# pcb-pick-plaz-control_v1e.net
KiCad netlist of a schematic drawn in EAGLE
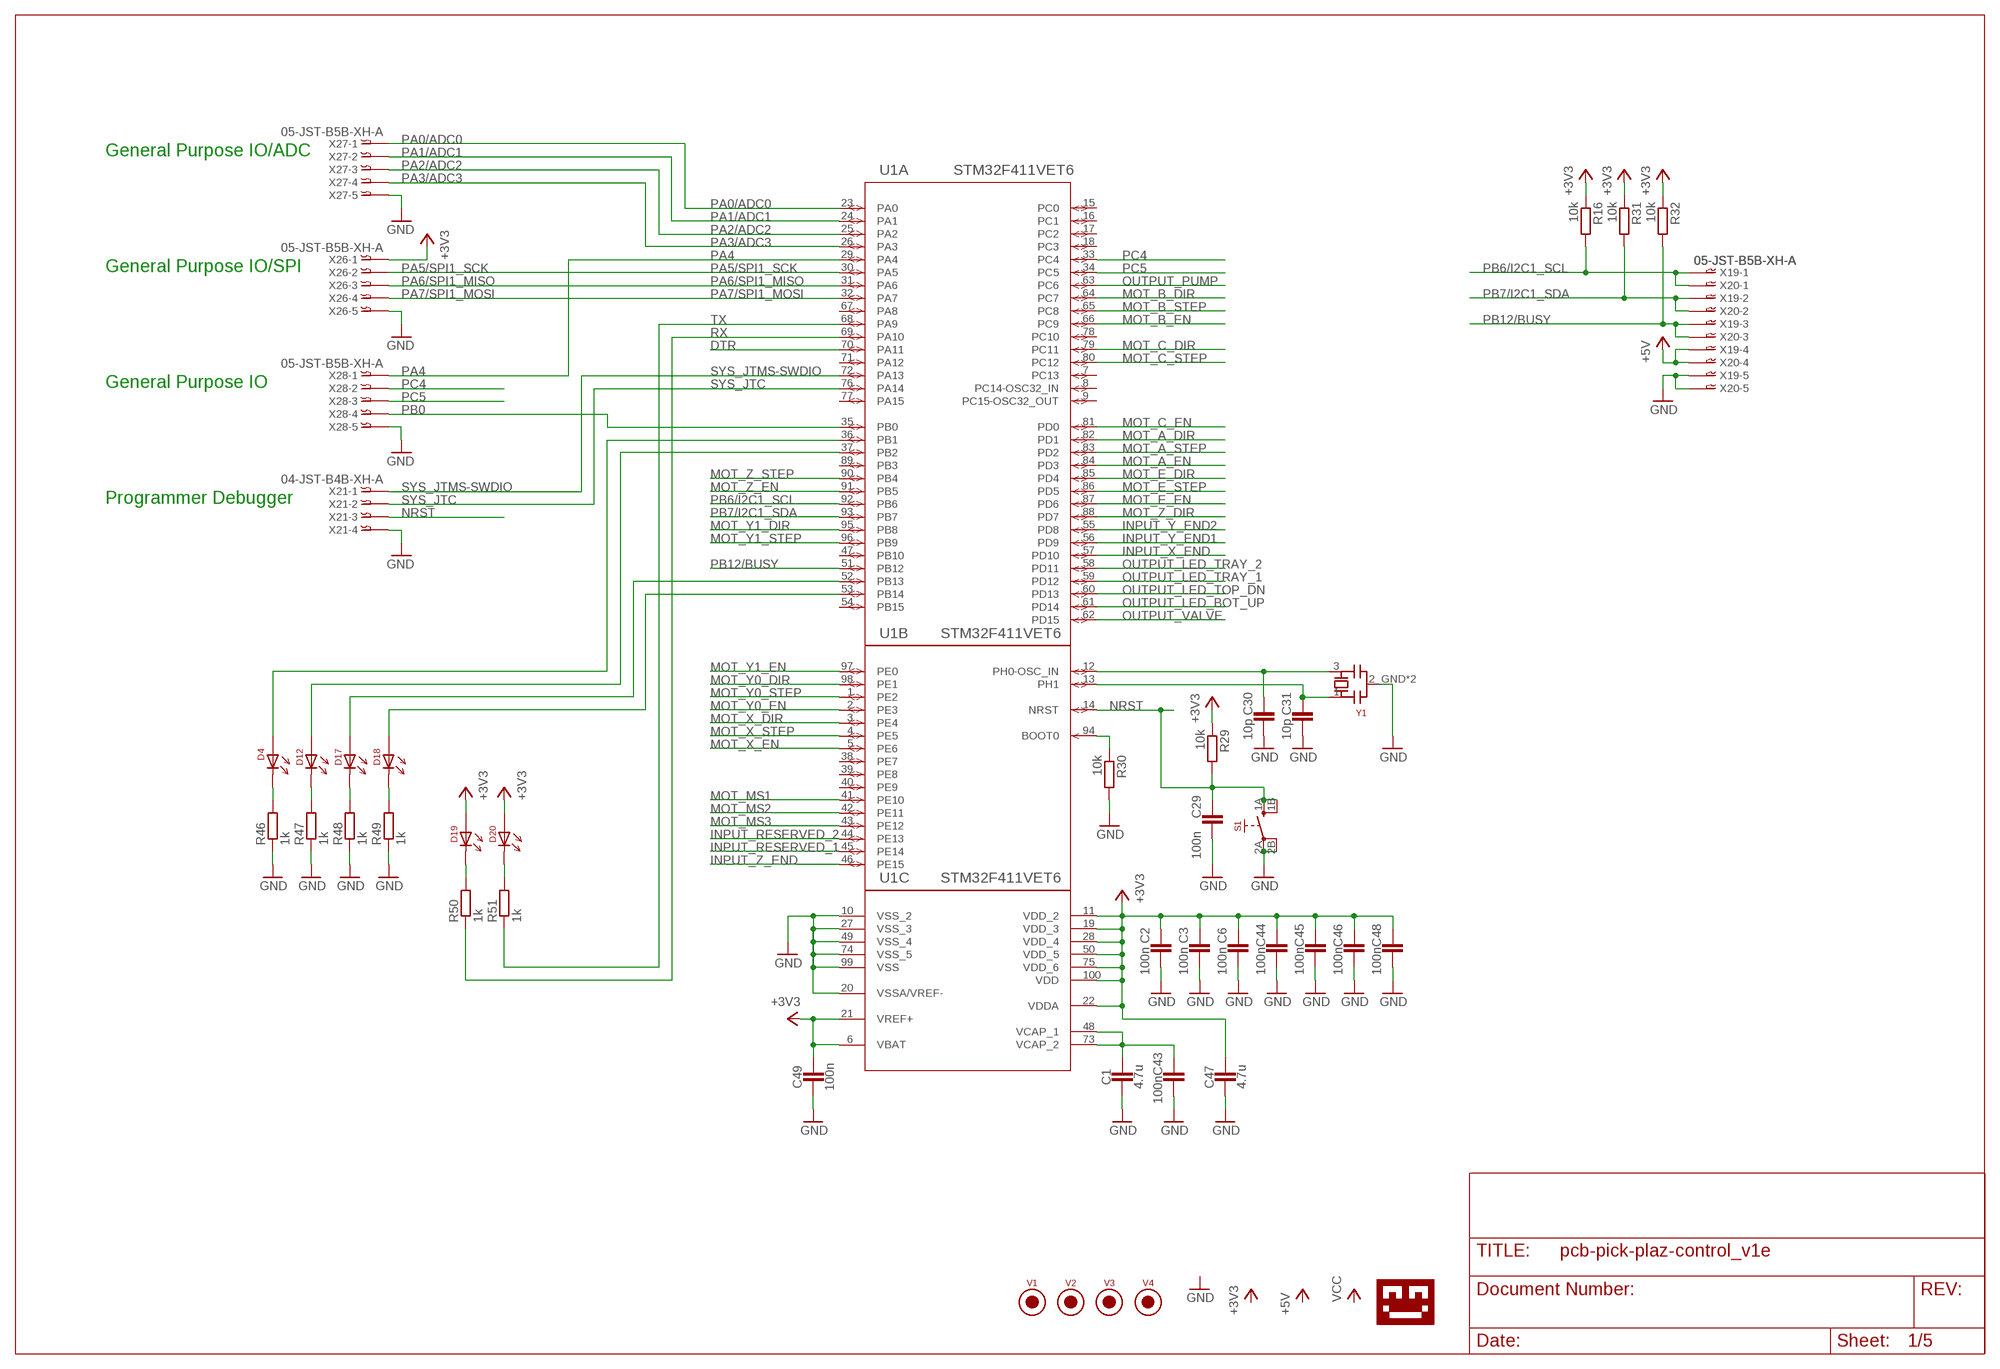
[diagram p0: schematic, sheet 1]
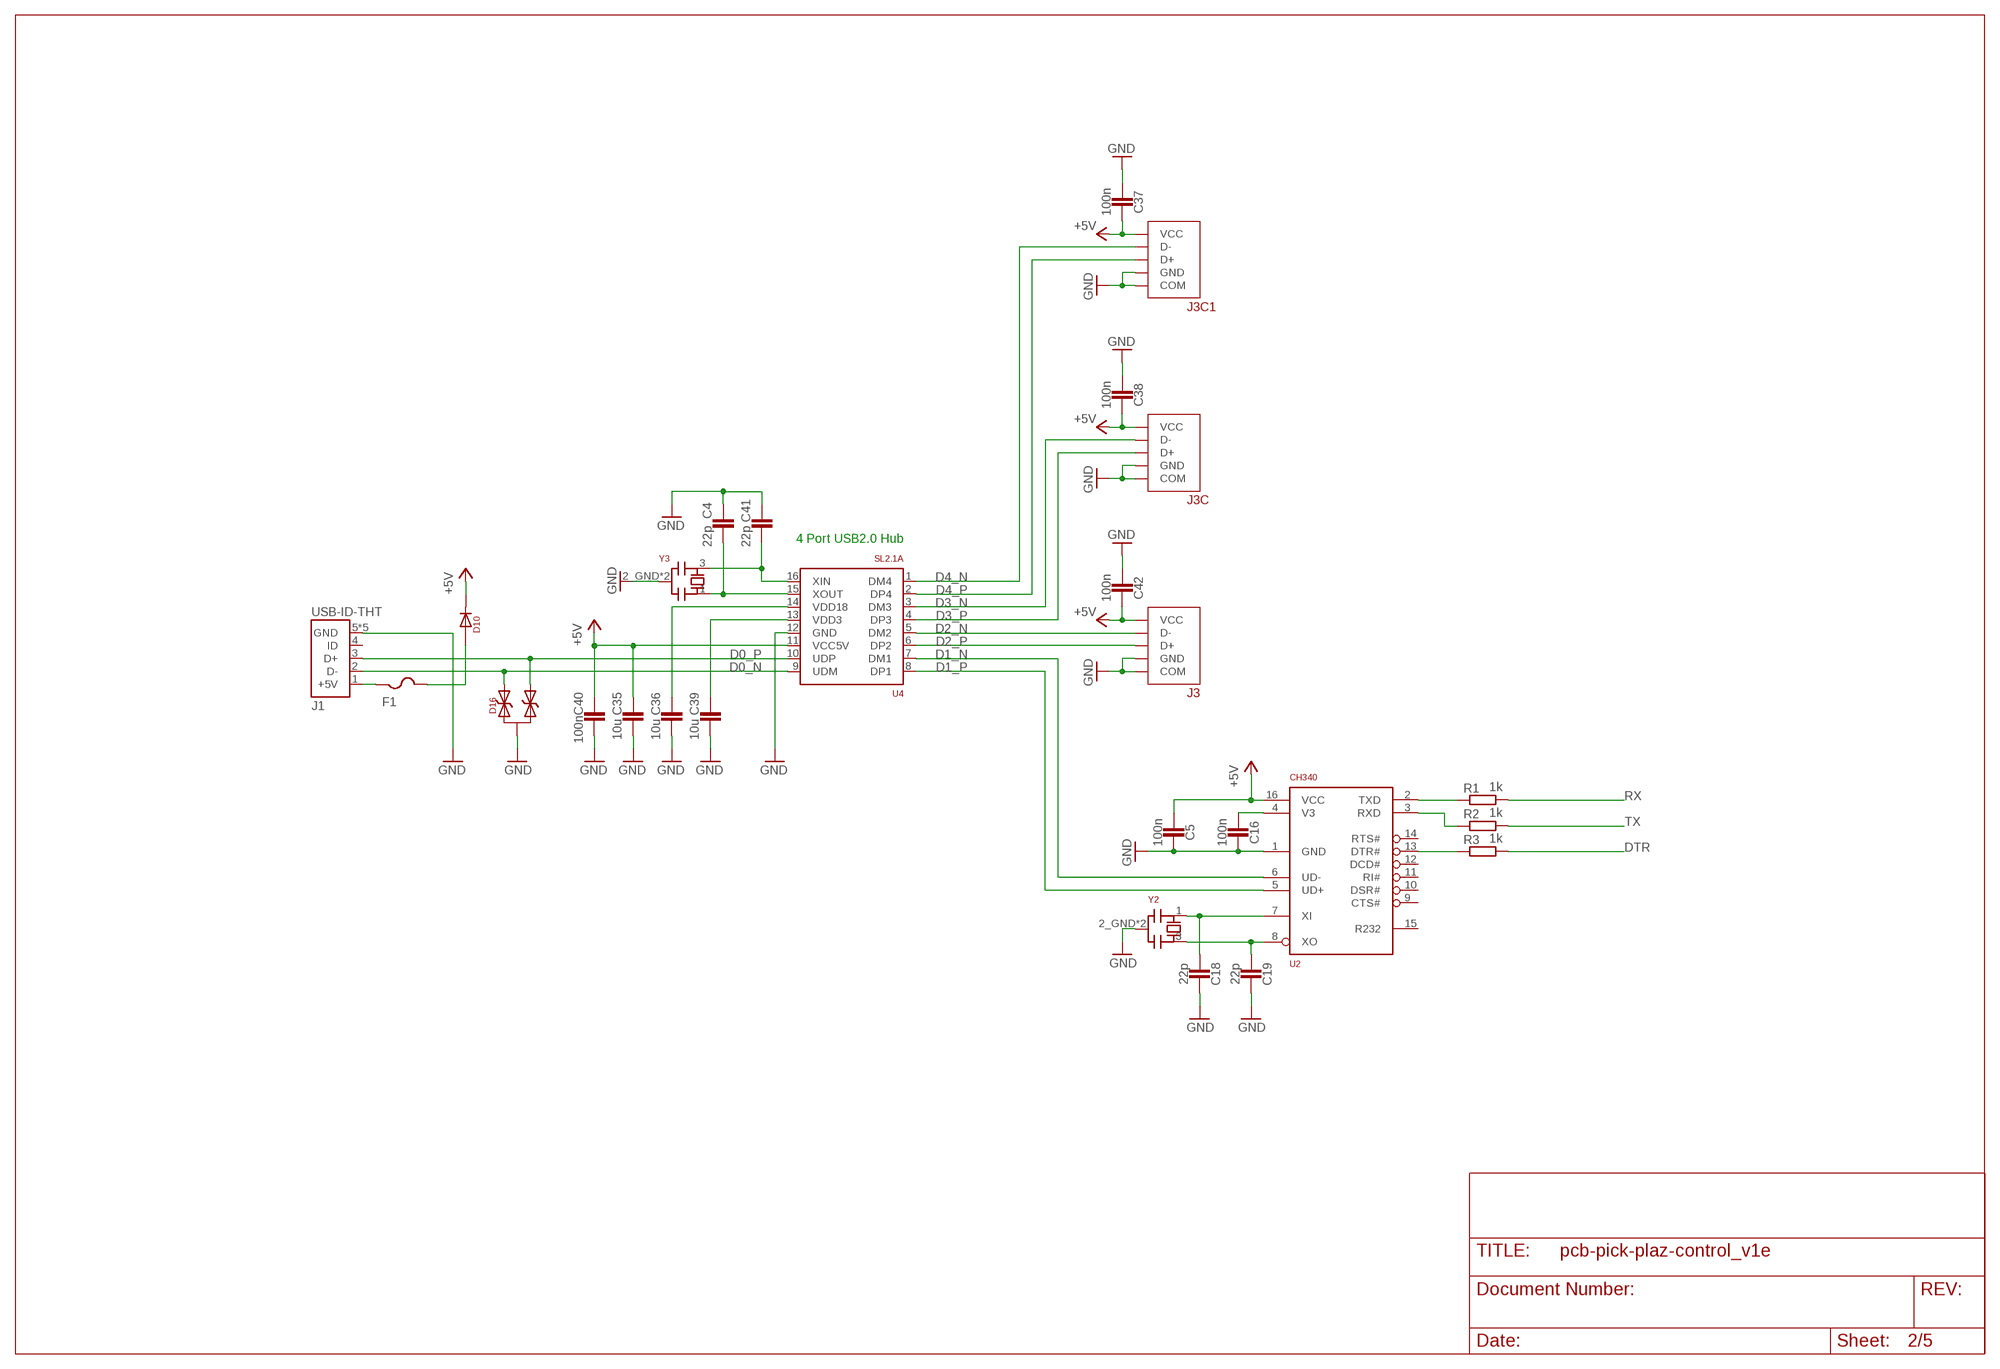
[diagram p1: schematic, sheet 2]
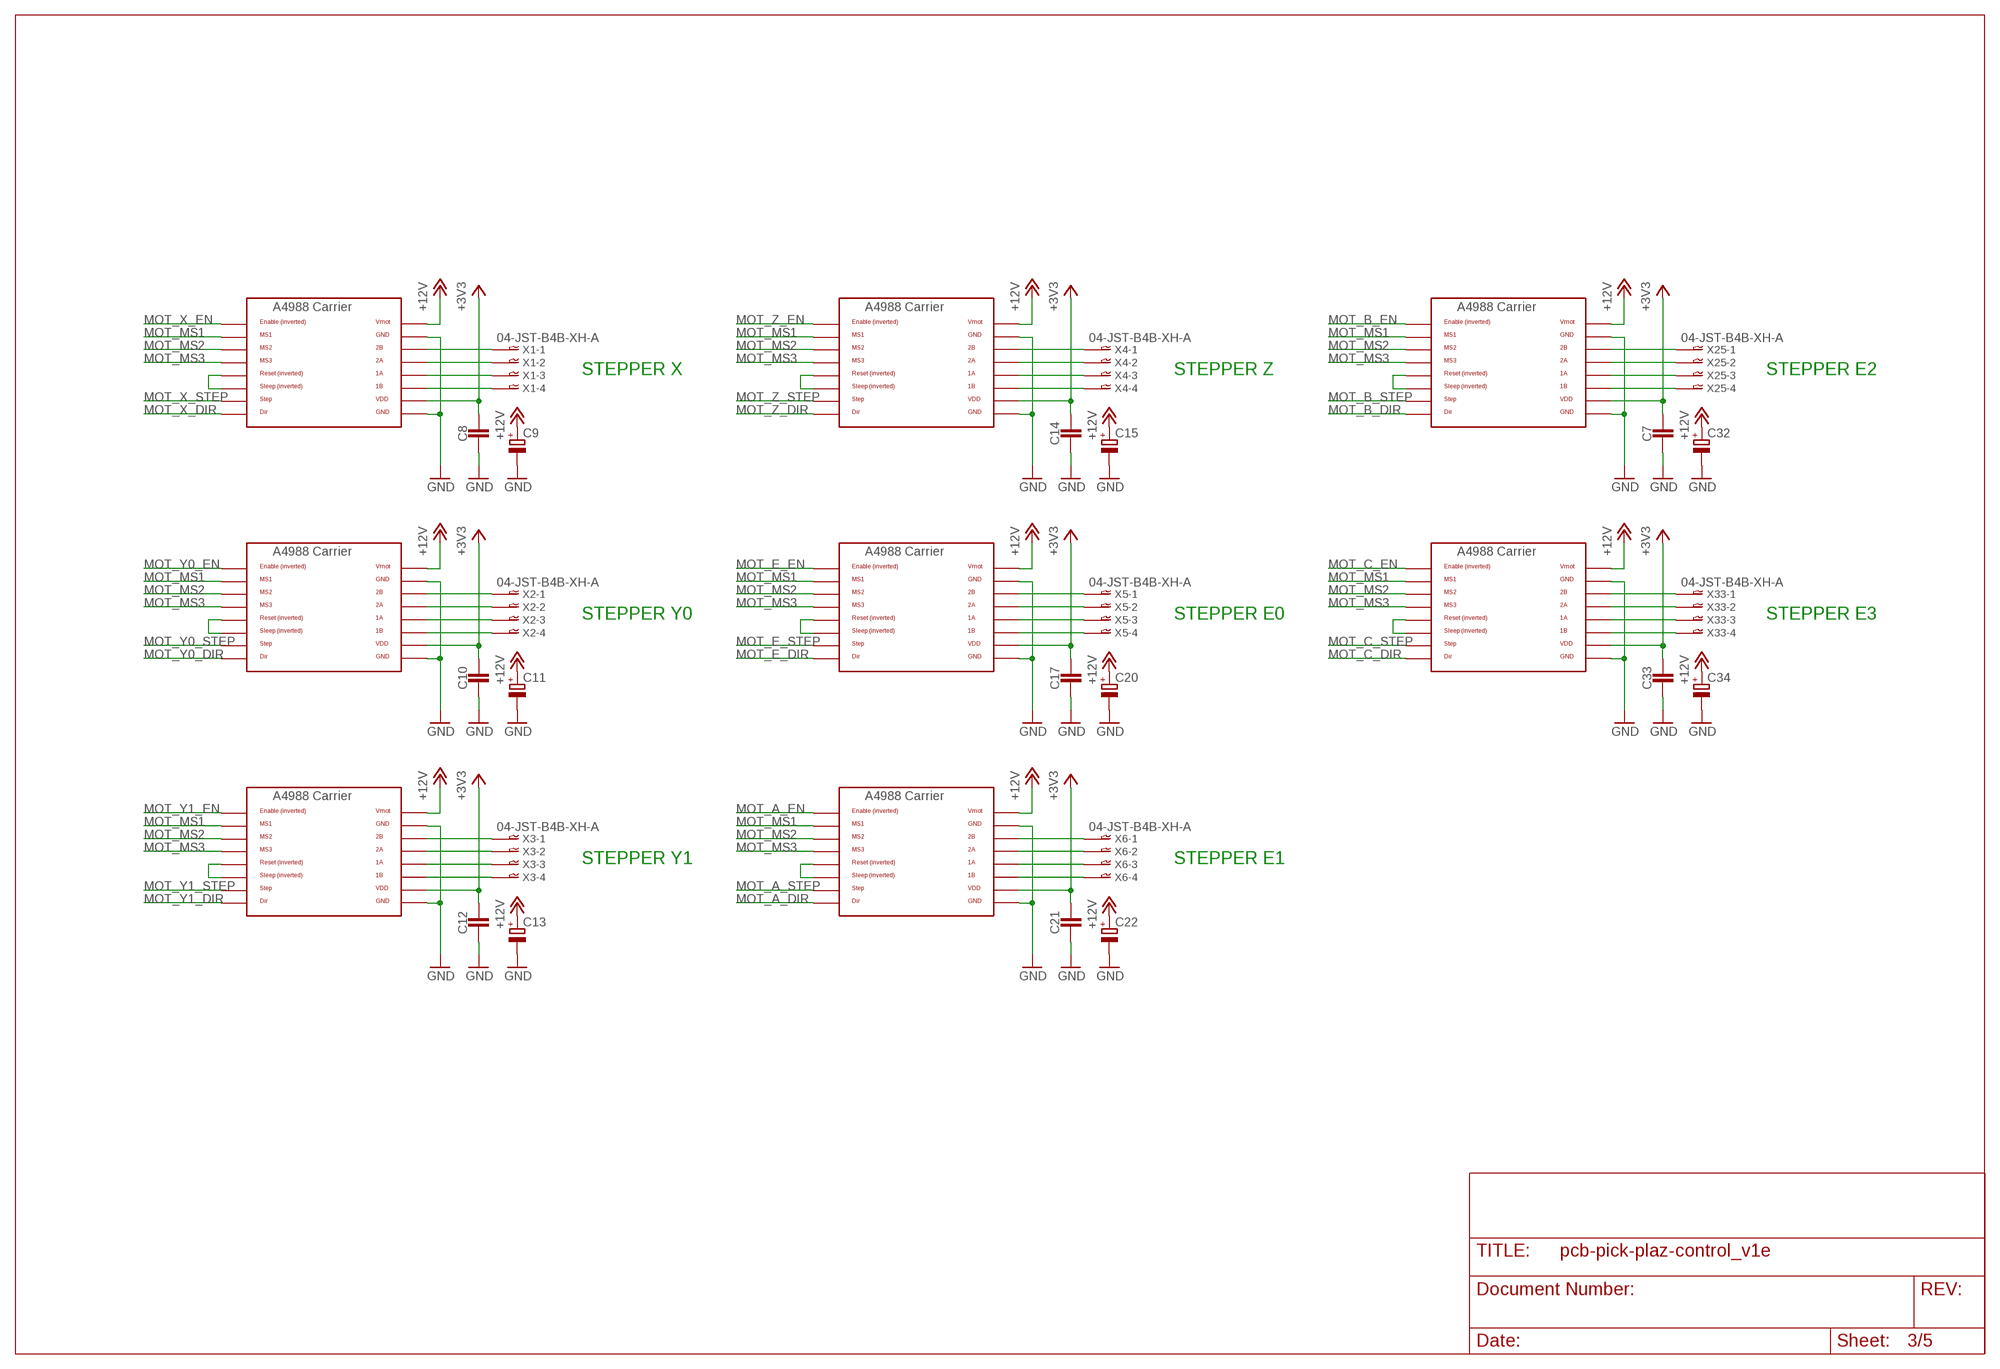
[diagram p2: schematic, sheet 3]
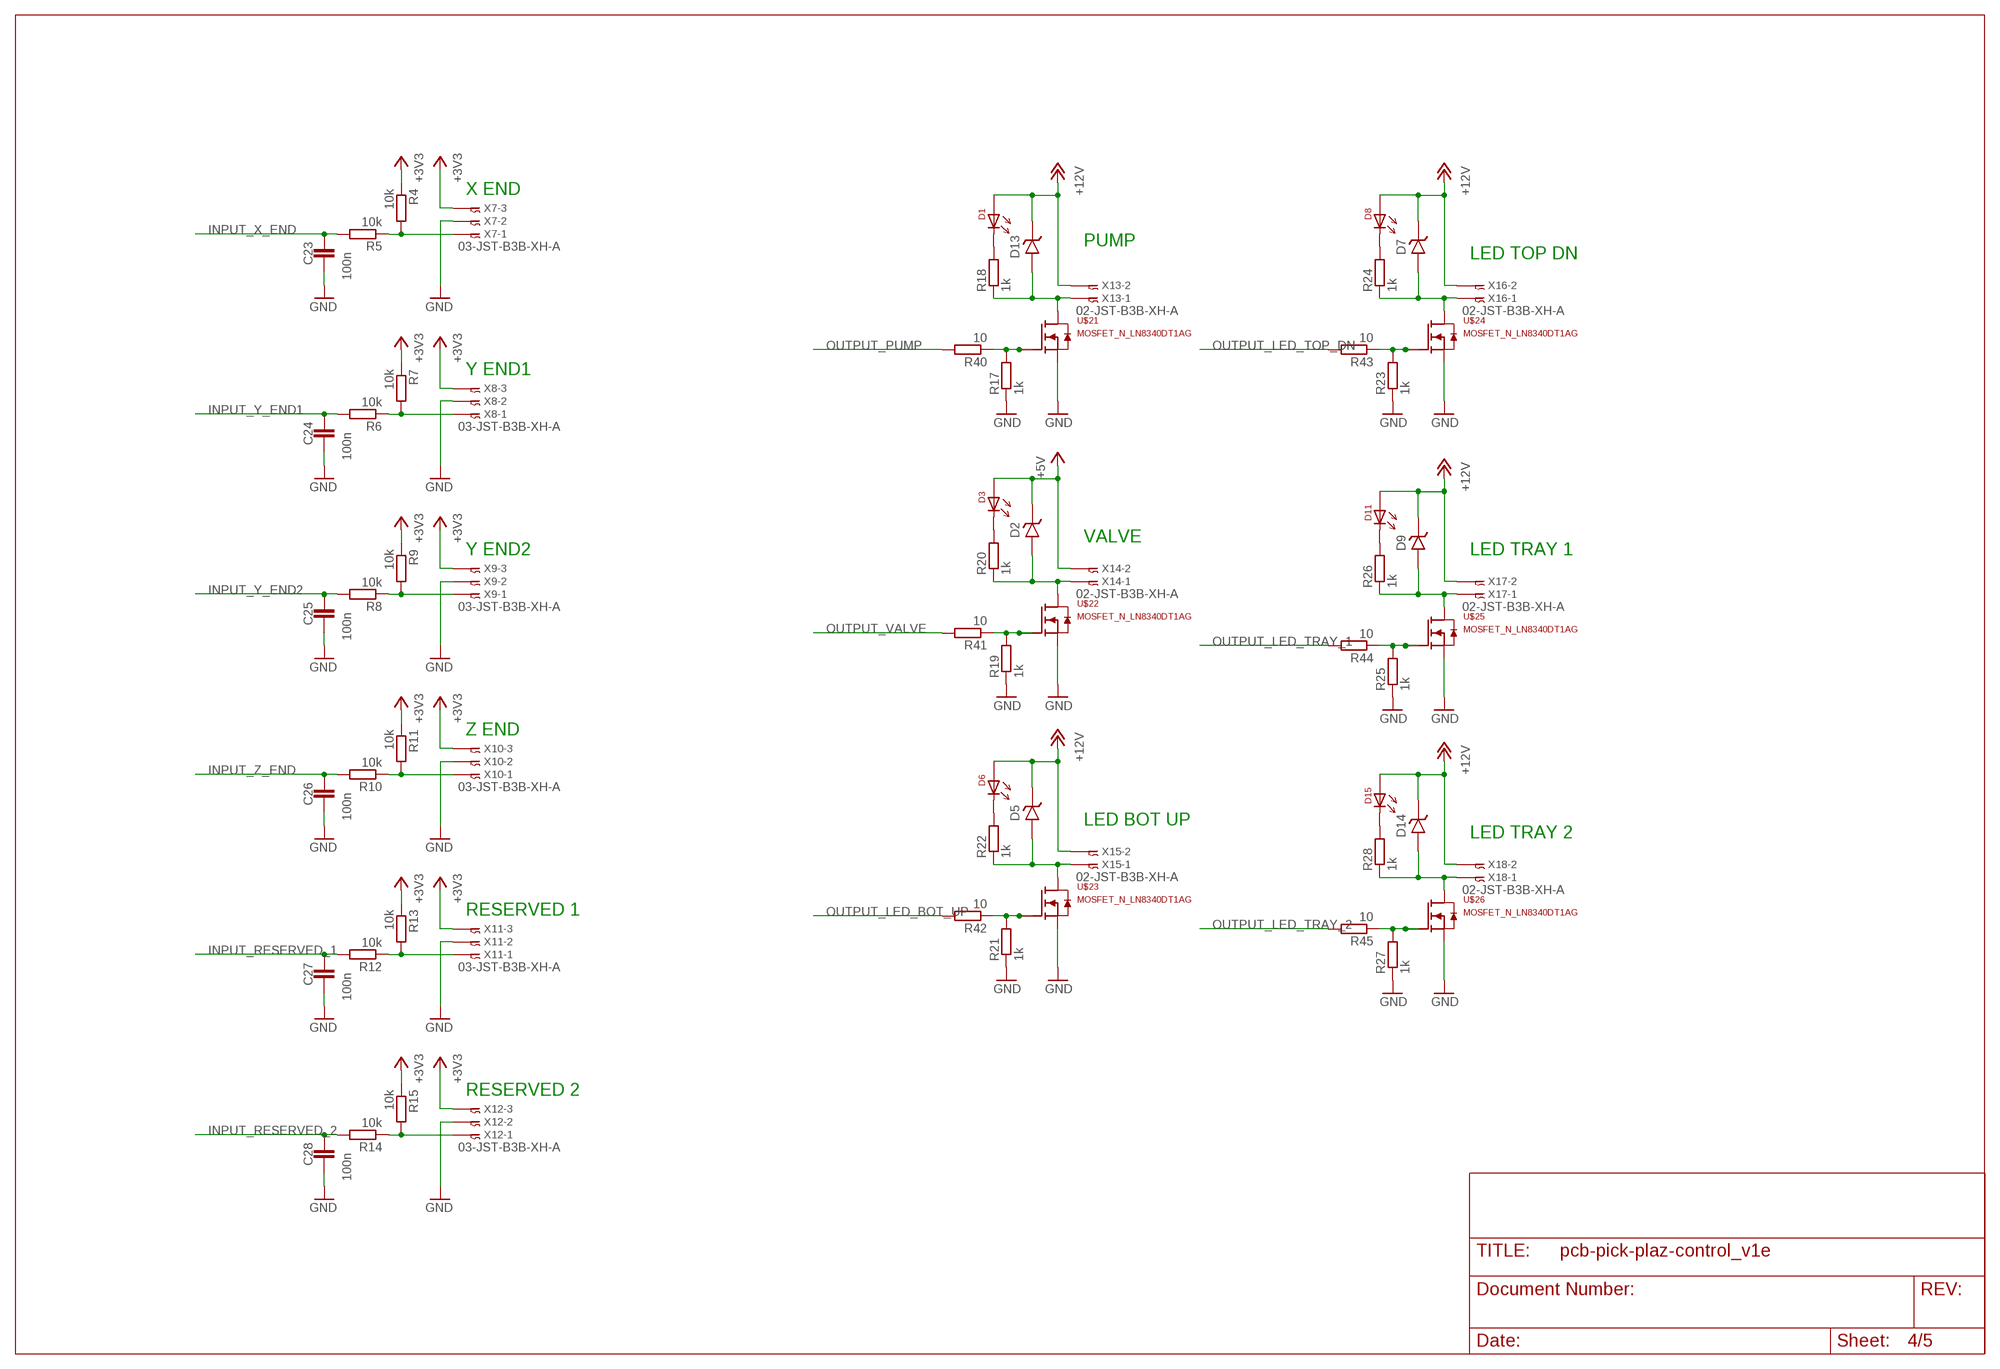
[diagram p3: schematic, sheet 4]
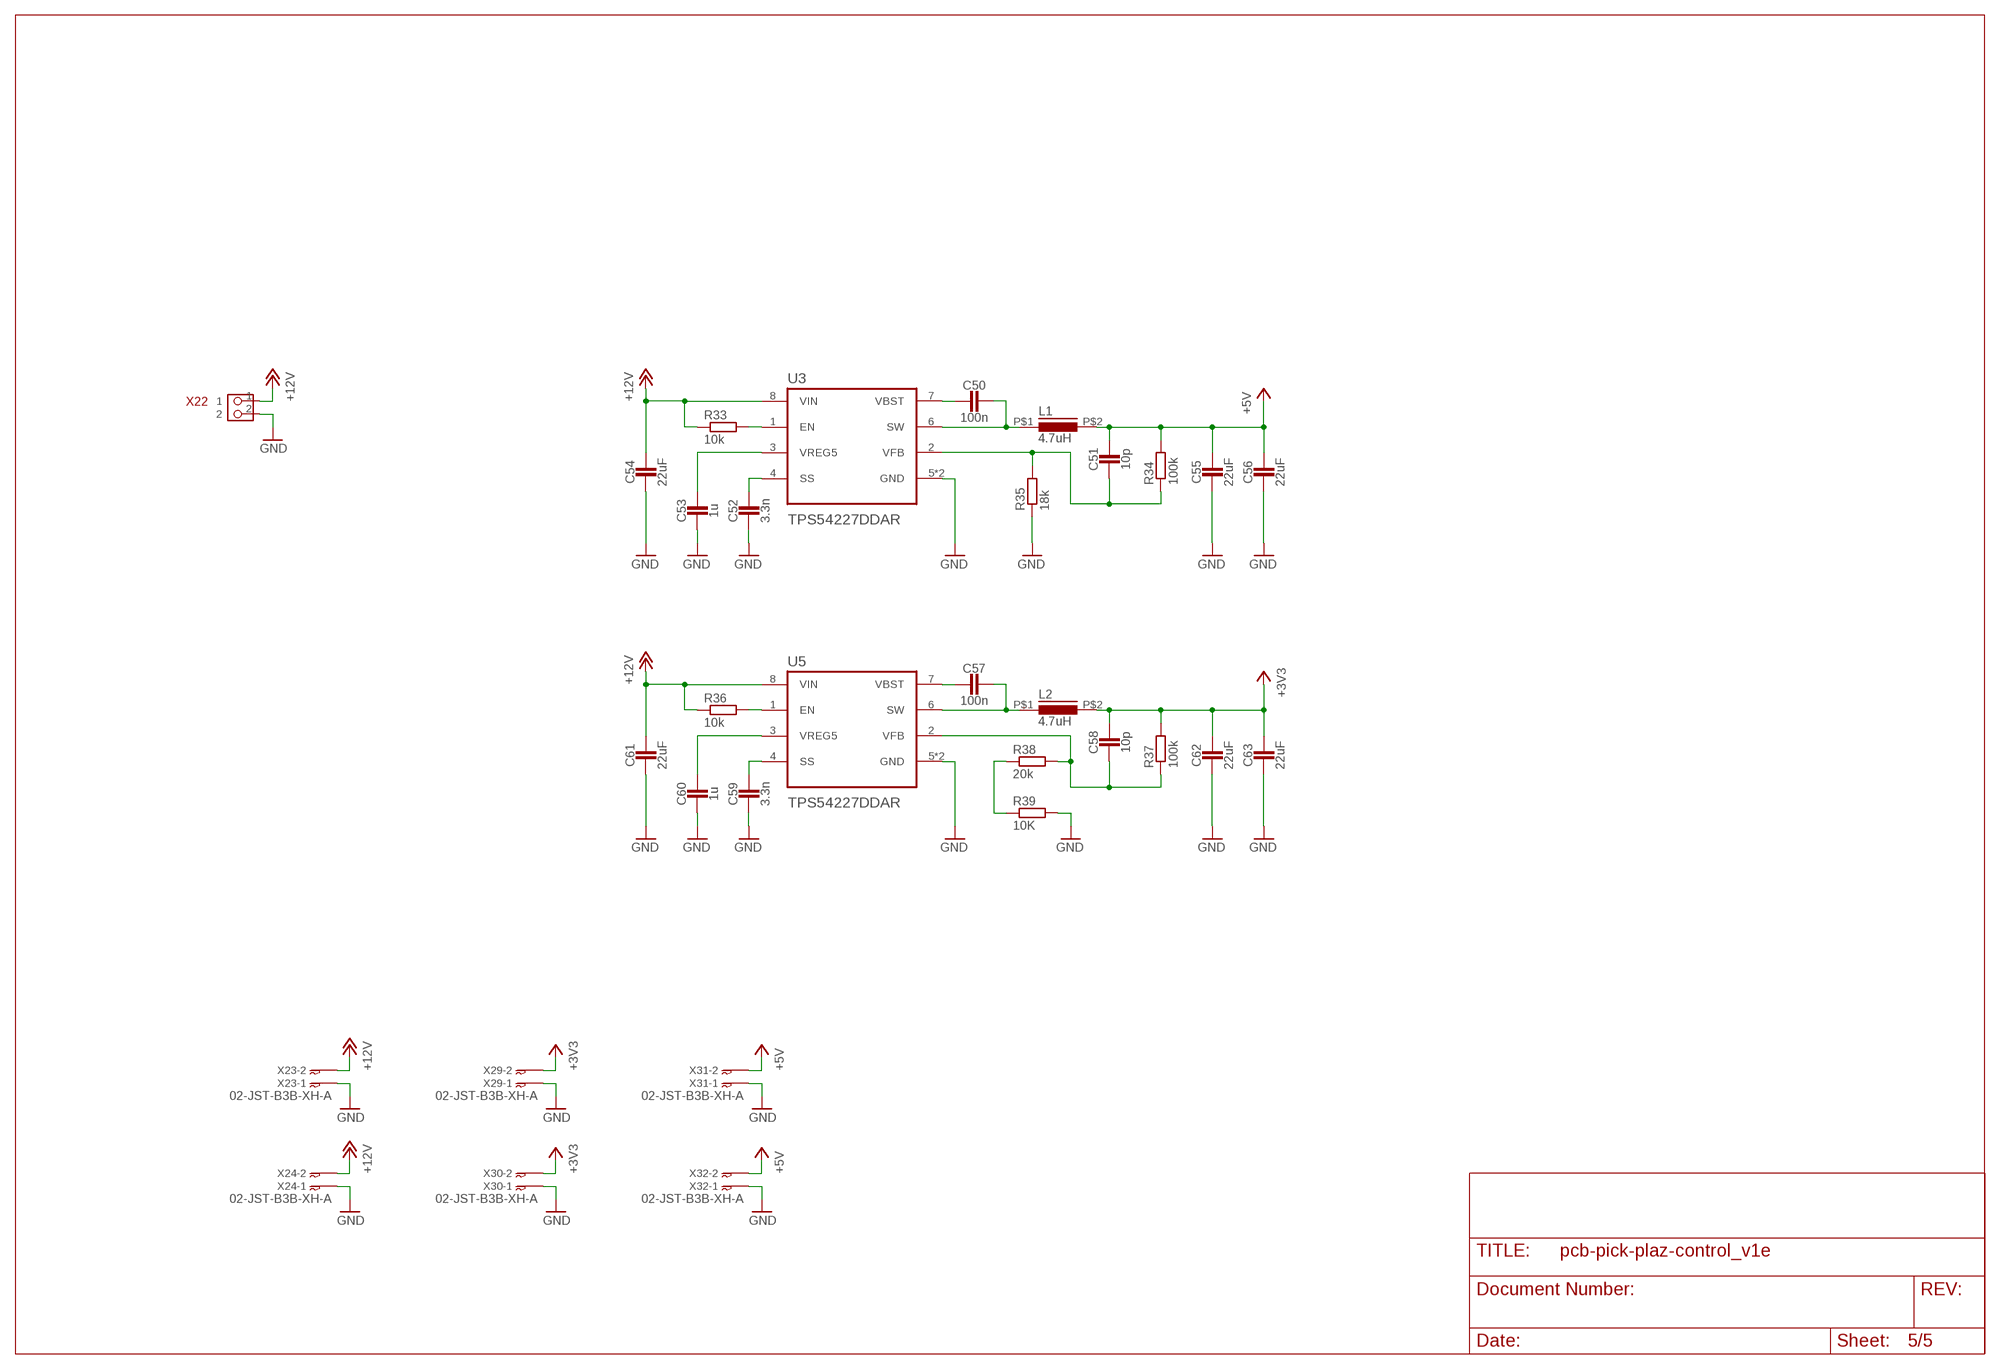
[diagram p4: schematic, sheet 5]

(export (version "E")
  (design (tool "Eeschema 10.0.6"))
  (components
    (comp (ref "C23")
      (value "100n")
      (footprint "eagle-import:0603_CAP")
      (libsource (lib "eagle-import") (part "CAPACITOR0603_CAP"))
    )
    (comp (ref "C24")
      (value "100n")
      (footprint "eagle-import:0603_CAP")
      (libsource (lib "eagle-import") (part "CAPACITOR0603_CAP"))
    )
    (comp (ref "C25")
      (value "100n")
      (footprint "eagle-import:0603_CAP")
      (libsource (lib "eagle-import") (part "CAPACITOR0603_CAP"))
    )
    (comp (ref "C26")
      (value "100n")
      (footprint "eagle-import:0603_CAP")
      (libsource (lib "eagle-import") (part "CAPACITOR0603_CAP"))
    )
    (comp (ref "C27")
      (value "100n")
      (footprint "eagle-import:0603_CAP")
      (libsource (lib "eagle-import") (part "CAPACITOR0603_CAP"))
    )
    (comp (ref "C28")
      (value "100n")
      (footprint "eagle-import:0603_CAP")
      (libsource (lib "eagle-import") (part "CAPACITOR0603_CAP"))
    )
    (comp (ref "D1")
      (value "LED-0805")
      (footprint "eagle-import:0805-DOT")
      (libsource (lib "eagle-import") (part "LED-0805"))
    )
    (comp (ref "D2")
      (value "DIODE_ZENERSOD123")
      (footprint "eagle-import:SOD123")
      (libsource (lib "eagle-import") (part "DIODE_ZENERSOD123"))
    )
    (comp (ref "D3")
      (value "LED-0805")
      (footprint "eagle-import:0805-DOT")
      (libsource (lib "eagle-import") (part "LED-0805"))
    )
    (comp (ref "D5")
      (value "DIODE_ZENERSOD123")
      (footprint "eagle-import:SOD123")
      (libsource (lib "eagle-import") (part "DIODE_ZENERSOD123"))
    )
    (comp (ref "D6")
      (value "LED-0805")
      (footprint "eagle-import:0805-DOT")
      (libsource (lib "eagle-import") (part "LED-0805"))
    )
    (comp (ref "D7")
      (value "DIODE_ZENERSOD123")
      (footprint "eagle-import:SOD123")
      (libsource (lib "eagle-import") (part "DIODE_ZENERSOD123"))
    )
    (comp (ref "D8")
      (value "LED-0805")
      (footprint "eagle-import:0805-DOT")
      (libsource (lib "eagle-import") (part "LED-0805"))
    )
    (comp (ref "D9")
      (value "DIODE_ZENERSOD123")
      (footprint "eagle-import:SOD123")
      (libsource (lib "eagle-import") (part "DIODE_ZENERSOD123"))
    )
    (comp (ref "D11")
      (value "LED-0805")
      (footprint "eagle-import:0805-DOT")
      (libsource (lib "eagle-import") (part "LED-0805"))
    )
    (comp (ref "D13")
      (value "DIODE_ZENERSOD123")
      (footprint "eagle-import:SOD123")
      (libsource (lib "eagle-import") (part "DIODE_ZENERSOD123"))
    )
    (comp (ref "D14")
      (value "DIODE_ZENERSOD123")
      (footprint "eagle-import:SOD123")
      (libsource (lib "eagle-import") (part "DIODE_ZENERSOD123"))
    )
    (comp (ref "D15")
      (value "LED-0805")
      (footprint "eagle-import:0805-DOT")
      (libsource (lib "eagle-import") (part "LED-0805"))
    )
    (comp (ref "R4")
      (value "10k")
      (footprint "eagle-import:0603-RES")
      (libsource (lib "eagle-import") (part "RESISTOR0603_RES"))
    )
    (comp (ref "R5")
      (value "10k")
      (footprint "eagle-import:0603-RES")
      (libsource (lib "eagle-import") (part "RESISTOR0603_RES"))
    )
    (comp (ref "R6")
      (value "10k")
      (footprint "eagle-import:0603-RES")
      (libsource (lib "eagle-import") (part "RESISTOR0603_RES"))
    )
    (comp (ref "R7")
      (value "10k")
      (footprint "eagle-import:0603-RES")
      (libsource (lib "eagle-import") (part "RESISTOR0603_RES"))
    )
    (comp (ref "R8")
      (value "10k")
      (footprint "eagle-import:0603-RES")
      (libsource (lib "eagle-import") (part "RESISTOR0603_RES"))
    )
    (comp (ref "R9")
      (value "10k")
      (footprint "eagle-import:0603-RES")
      (libsource (lib "eagle-import") (part "RESISTOR0603_RES"))
    )
    (comp (ref "R10")
      (value "10k")
      (footprint "eagle-import:0603-RES")
      (libsource (lib "eagle-import") (part "RESISTOR0603_RES"))
    )
    (comp (ref "R11")
      (value "10k")
      (footprint "eagle-import:0603-RES")
      (libsource (lib "eagle-import") (part "RESISTOR0603_RES"))
    )
    (comp (ref "R12")
      (value "10k")
      (footprint "eagle-import:0603-RES")
      (libsource (lib "eagle-import") (part "RESISTOR0603_RES"))
    )
    (comp (ref "R13")
      (value "10k")
      (footprint "eagle-import:0603-RES")
      (libsource (lib "eagle-import") (part "RESISTOR0603_RES"))
    )
    (comp (ref "R14")
      (value "10k")
      (footprint "eagle-import:0603-RES")
      (libsource (lib "eagle-import") (part "RESISTOR0603_RES"))
    )
    (comp (ref "R15")
      (value "10k")
      (footprint "eagle-import:0603-RES")
      (libsource (lib "eagle-import") (part "RESISTOR0603_RES"))
    )
    (comp (ref "R17")
      (value "1k")
      (footprint "eagle-import:0603-RES")
      (libsource (lib "eagle-import") (part "RESISTOR0603_RES"))
    )
    (comp (ref "R18")
      (value "1k")
      (footprint "eagle-import:0603-RES")
      (libsource (lib "eagle-import") (part "RESISTOR0603_RES"))
    )
    (comp (ref "R19")
      (value "1k")
      (footprint "eagle-import:0603-RES")
      (libsource (lib "eagle-import") (part "RESISTOR0603_RES"))
    )
    (comp (ref "R20")
      (value "1k")
      (footprint "eagle-import:0603-RES")
      (libsource (lib "eagle-import") (part "RESISTOR0603_RES"))
    )
    (comp (ref "R21")
      (value "1k")
      (footprint "eagle-import:0603-RES")
      (libsource (lib "eagle-import") (part "RESISTOR0603_RES"))
    )
    (comp (ref "R22")
      (value "1k")
      (footprint "eagle-import:0603-RES")
      (libsource (lib "eagle-import") (part "RESISTOR0603_RES"))
    )
    (comp (ref "R23")
      (value "1k")
      (footprint "eagle-import:0603-RES")
      (libsource (lib "eagle-import") (part "RESISTOR0603_RES"))
    )
    (comp (ref "R24")
      (value "1k")
      (footprint "eagle-import:0603-RES")
      (libsource (lib "eagle-import") (part "RESISTOR0603_RES"))
    )
    (comp (ref "R25")
      (value "1k")
      (footprint "eagle-import:0603-RES")
      (libsource (lib "eagle-import") (part "RESISTOR0603_RES"))
    )
    (comp (ref "R26")
      (value "1k")
      (footprint "eagle-import:0603-RES")
      (libsource (lib "eagle-import") (part "RESISTOR0603_RES"))
    )
    (comp (ref "R27")
      (value "1k")
      (footprint "eagle-import:0603-RES")
      (libsource (lib "eagle-import") (part "RESISTOR0603_RES"))
    )
    (comp (ref "R28")
      (value "1k")
      (footprint "eagle-import:0603-RES")
      (libsource (lib "eagle-import") (part "RESISTOR0603_RES"))
    )
    (comp (ref "R40")
      (value "10")
      (footprint "eagle-import:0603-RES")
      (libsource (lib "eagle-import") (part "RESISTOR0603_RES"))
    )
    (comp (ref "R41")
      (value "10")
      (footprint "eagle-import:0603-RES")
      (libsource (lib "eagle-import") (part "RESISTOR0603_RES"))
    )
    (comp (ref "R42")
      (value "10")
      (footprint "eagle-import:0603-RES")
      (libsource (lib "eagle-import") (part "RESISTOR0603_RES"))
    )
    (comp (ref "R43")
      (value "10")
      (footprint "eagle-import:0603-RES")
      (libsource (lib "eagle-import") (part "RESISTOR0603_RES"))
    )
    (comp (ref "R44")
      (value "10")
      (footprint "eagle-import:0603-RES")
      (libsource (lib "eagle-import") (part "RESISTOR0603_RES"))
    )
    (comp (ref "R45")
      (value "10")
      (footprint "eagle-import:0603-RES")
      (libsource (lib "eagle-import") (part "RESISTOR0603_RES"))
    )
    (comp (ref "U$21")
      (value "MOSFET_N_LN8340DT1AG")
      (footprint "eagle-import:DFN3030-8B")
      (libsource (lib "eagle-import") (part "MOSFET_N_LN8340DT1AG"))
    )
    (comp (ref "U$22")
      (value "MOSFET_N_LN8340DT1AG")
      (footprint "eagle-import:DFN3030-8B")
      (libsource (lib "eagle-import") (part "MOSFET_N_LN8340DT1AG"))
    )
    (comp (ref "U$23")
      (value "MOSFET_N_LN8340DT1AG")
      (footprint "eagle-import:DFN3030-8B")
      (libsource (lib "eagle-import") (part "MOSFET_N_LN8340DT1AG"))
    )
    (comp (ref "U$24")
      (value "MOSFET_N_LN8340DT1AG")
      (footprint "eagle-import:DFN3030-8B")
      (libsource (lib "eagle-import") (part "MOSFET_N_LN8340DT1AG"))
    )
    (comp (ref "U$25")
      (value "MOSFET_N_LN8340DT1AG")
      (footprint "eagle-import:DFN3030-8B")
      (libsource (lib "eagle-import") (part "MOSFET_N_LN8340DT1AG"))
    )
    (comp (ref "U$26")
      (value "MOSFET_N_LN8340DT1AG")
      (footprint "eagle-import:DFN3030-8B")
      (libsource (lib "eagle-import") (part "MOSFET_N_LN8340DT1AG"))
    )
    (comp (ref "X7")
      (value "03-JST-B3B-XH-A")
      (footprint "eagle-import:B3B-XH")
      (libsource (lib "eagle-import") (part "03-JST-B3B-XH-A"))
    )
    (comp (ref "X8")
      (value "03-JST-B3B-XH-A")
      (footprint "eagle-import:B3B-XH")
      (libsource (lib "eagle-import") (part "03-JST-B3B-XH-A"))
    )
    (comp (ref "X9")
      (value "03-JST-B3B-XH-A")
      (footprint "eagle-import:B3B-XH")
      (libsource (lib "eagle-import") (part "03-JST-B3B-XH-A"))
    )
    (comp (ref "X10")
      (value "03-JST-B3B-XH-A")
      (footprint "eagle-import:B3B-XH")
      (libsource (lib "eagle-import") (part "03-JST-B3B-XH-A"))
    )
    (comp (ref "X11")
      (value "03-JST-B3B-XH-A")
      (footprint "eagle-import:B3B-XH")
      (libsource (lib "eagle-import") (part "03-JST-B3B-XH-A"))
    )
    (comp (ref "X12")
      (value "03-JST-B3B-XH-A")
      (footprint "eagle-import:B3B-XH")
      (libsource (lib "eagle-import") (part "03-JST-B3B-XH-A"))
    )
    (comp (ref "X13")
      (value "02-JST-B3B-XH-A")
      (footprint "eagle-import:B2B-XH")
      (libsource (lib "eagle-import") (part "02-JST-B3B-XH-A"))
    )
    (comp (ref "X14")
      (value "02-JST-B3B-XH-A")
      (footprint "eagle-import:B2B-XH")
      (libsource (lib "eagle-import") (part "02-JST-B3B-XH-A"))
    )
    (comp (ref "X15")
      (value "02-JST-B3B-XH-A")
      (footprint "eagle-import:B2B-XH")
      (libsource (lib "eagle-import") (part "02-JST-B3B-XH-A"))
    )
    (comp (ref "X16")
      (value "02-JST-B3B-XH-A")
      (footprint "eagle-import:B2B-XH")
      (libsource (lib "eagle-import") (part "02-JST-B3B-XH-A"))
    )
    (comp (ref "X17")
      (value "02-JST-B3B-XH-A")
      (footprint "eagle-import:B2B-XH")
      (libsource (lib "eagle-import") (part "02-JST-B3B-XH-A"))
    )
    (comp (ref "X18")
      (value "02-JST-B3B-XH-A")
      (footprint "eagle-import:B2B-XH")
      (libsource (lib "eagle-import") (part "02-JST-B3B-XH-A"))
    )
    (comp (ref "C50")
      (value "100n")
      (footprint "eagle-import:0603_CAP")
      (libsource (lib "eagle-import") (part "CAPACITOR0603_CAP"))
    )
    (comp (ref "C51")
      (value "10p")
      (footprint "eagle-import:0603_CAP")
      (libsource (lib "eagle-import") (part "CAPACITOR0603_CAP"))
    )
    (comp (ref "C52")
      (value "3.3n")
      (footprint "eagle-import:0603_CAP")
      (libsource (lib "eagle-import") (part "CAPACITOR0603_CAP"))
    )
    (comp (ref "C53")
      (value "1u")
      (footprint "eagle-import:0603_CAP")
      (libsource (lib "eagle-import") (part "CAPACITOR0603_CAP"))
    )
    (comp (ref "C54")
      (value "22uF")
      (footprint "eagle-import:1206_CAP")
      (libsource (lib "eagle-import") (part "CAPACITOR1206_CAP"))
    )
    (comp (ref "C55")
      (value "22uF")
      (footprint "eagle-import:0805_CAP")
      (libsource (lib "eagle-import") (part "CAPACITOR0805_CAP"))
    )
    (comp (ref "C56")
      (value "22uF")
      (footprint "eagle-import:0805_CAP")
      (libsource (lib "eagle-import") (part "CAPACITOR0805_CAP"))
    )
    (comp (ref "C57")
      (value "100n")
      (footprint "eagle-import:0603_CAP")
      (libsource (lib "eagle-import") (part "CAPACITOR0603_CAP"))
    )
    (comp (ref "C58")
      (value "10p")
      (footprint "eagle-import:0603_CAP")
      (libsource (lib "eagle-import") (part "CAPACITOR0603_CAP"))
    )
    (comp (ref "C59")
      (value "3.3n")
      (footprint "eagle-import:0603_CAP")
      (libsource (lib "eagle-import") (part "CAPACITOR0603_CAP"))
    )
    (comp (ref "C60")
      (value "1u")
      (footprint "eagle-import:0603_CAP")
      (libsource (lib "eagle-import") (part "CAPACITOR0603_CAP"))
    )
    (comp (ref "C61")
      (value "22uF")
      (footprint "eagle-import:1206_CAP")
      (libsource (lib "eagle-import") (part "CAPACITOR1206_CAP"))
    )
    (comp (ref "C62")
      (value "22uF")
      (footprint "eagle-import:0805_CAP")
      (libsource (lib "eagle-import") (part "CAPACITOR0805_CAP"))
    )
    (comp (ref "C63")
      (value "22uF")
      (footprint "eagle-import:0805_CAP")
      (libsource (lib "eagle-import") (part "CAPACITOR0805_CAP"))
    )
    (comp (ref "L1")
      (value "4.7uH")
      (footprint "eagle-import:IND_CR4")
      (libsource (lib "eagle-import") (part "INDUCTOR"))
    )
    (comp (ref "L2")
      (value "4.7uH")
      (footprint "eagle-import:IND_CR4")
      (libsource (lib "eagle-import") (part "INDUCTOR"))
    )
    (comp (ref "R33")
      (value "10k")
      (footprint "eagle-import:0603-RES")
      (libsource (lib "eagle-import") (part "RESISTOR0603_RES"))
    )
    (comp (ref "R34")
      (value "100k")
      (footprint "eagle-import:0603-RES")
      (libsource (lib "eagle-import") (part "RESISTOR0603_RES"))
    )
    (comp (ref "R35")
      (value "18k")
      (footprint "eagle-import:0603-RES")
      (libsource (lib "eagle-import") (part "RESISTOR0603_RES"))
    )
    (comp (ref "R36")
      (value "10k")
      (footprint "eagle-import:0603-RES")
      (libsource (lib "eagle-import") (part "RESISTOR0603_RES"))
    )
    (comp (ref "R37")
      (value "100k")
      (footprint "eagle-import:0603-RES")
      (libsource (lib "eagle-import") (part "RESISTOR0603_RES"))
    )
    (comp (ref "R38")
      (value "20k")
      (footprint "eagle-import:0603-RES")
      (libsource (lib "eagle-import") (part "RESISTOR0603_RES"))
    )
    (comp (ref "R39")
      (value "10K")
      (footprint "eagle-import:0603-RES")
      (libsource (lib "eagle-import") (part "RESISTOR0603_RES"))
    )
    (comp (ref "U3")
      (value "TPS54227DDAR")
      (footprint "eagle-import:TPS54227DDAR_VREG_LM5017MR_NOPB")
      (fields (field (name "MF") "Texas Instruments"))
      (libsource (lib "eagle-import") (part "TPS54227DDAR"))
    )
    (comp (ref "U5")
      (value "TPS54227DDAR")
      (footprint "eagle-import:TPS54227DDAR_VREG_LM5017MR_NOPB")
      (fields (field (name "MF") "Texas Instruments"))
      (libsource (lib "eagle-import") (part "TPS54227DDAR"))
    )
    (comp (ref "X22")
      (value "PIN_2X13.81MM_LONGPAD")
      (footprint "eagle-import:PIN_2X1_3.81MM_LONGPAD")
      (libsource (lib "eagle-import") (part "PIN_2X13.81MM_LONGPAD"))
    )
    (comp (ref "X23")
      (value "02-JST-B3B-XH-A")
      (footprint "eagle-import:B2B-XH")
      (libsource (lib "eagle-import") (part "02-JST-B3B-XH-A"))
    )
    (comp (ref "X24")
      (value "02-JST-B3B-XH-A")
      (footprint "eagle-import:B2B-XH")
      (libsource (lib "eagle-import") (part "02-JST-B3B-XH-A"))
    )
    (comp (ref "X29")
      (value "02-JST-B3B-XH-A")
      (footprint "eagle-import:B2B-XH")
      (libsource (lib "eagle-import") (part "02-JST-B3B-XH-A"))
    )
    (comp (ref "X30")
      (value "02-JST-B3B-XH-A")
      (footprint "eagle-import:B2B-XH")
      (libsource (lib "eagle-import") (part "02-JST-B3B-XH-A"))
    )
    (comp (ref "X31")
      (value "02-JST-B3B-XH-A")
      (footprint "eagle-import:B2B-XH")
      (libsource (lib "eagle-import") (part "02-JST-B3B-XH-A"))
    )
    (comp (ref "X32")
      (value "02-JST-B3B-XH-A")
      (footprint "eagle-import:B2B-XH")
      (libsource (lib "eagle-import") (part "02-JST-B3B-XH-A"))
    )
    (comp (ref "C1")
      (value "4.7u")
      (footprint "eagle-import:0805_CAP")
      (libsource (lib "eagle-import") (part "CAPACITOR0805_CAP"))
    )
    (comp (ref "C2")
      (value "100n")
      (footprint "eagle-import:0603_CAP")
      (libsource (lib "eagle-import") (part "CAPACITOR0603_CAP"))
    )
    (comp (ref "C3")
      (value "100n")
      (footprint "eagle-import:0603_CAP")
      (libsource (lib "eagle-import") (part "CAPACITOR0603_CAP"))
    )
    (comp (ref "C6")
      (value "100n")
      (footprint "eagle-import:0603_CAP")
      (libsource (lib "eagle-import") (part "CAPACITOR0603_CAP"))
    )
    (comp (ref "C29")
      (value "100n")
      (footprint "eagle-import:0603_CAP")
      (libsource (lib "eagle-import") (part "CAPACITOR0603_CAP"))
    )
    (comp (ref "C30")
      (value "10p")
      (footprint "eagle-import:0603_CAP")
      (libsource (lib "eagle-import") (part "CAPACITOR0603_CAP"))
    )
    (comp (ref "C31")
      (value "10p")
      (footprint "eagle-import:0603_CAP")
      (libsource (lib "eagle-import") (part "CAPACITOR0603_CAP"))
    )
    (comp (ref "C43")
      (value "100n")
      (footprint "eagle-import:0603_CAP")
      (libsource (lib "eagle-import") (part "CAPACITOR0603_CAP"))
    )
    (comp (ref "C44")
      (value "100n")
      (footprint "eagle-import:0603_CAP")
      (libsource (lib "eagle-import") (part "CAPACITOR0603_CAP"))
    )
    (comp (ref "C45")
      (value "100n")
      (footprint "eagle-import:0603_CAP")
      (libsource (lib "eagle-import") (part "CAPACITOR0603_CAP"))
    )
    (comp (ref "C46")
      (value "100n")
      (footprint "eagle-import:0603_CAP")
      (libsource (lib "eagle-import") (part "CAPACITOR0603_CAP"))
    )
    (comp (ref "C47")
      (value "4.7u")
      (footprint "eagle-import:0805_CAP")
      (libsource (lib "eagle-import") (part "CAPACITOR0805_CAP"))
    )
    (comp (ref "C48")
      (value "100n")
      (footprint "eagle-import:0603_CAP")
      (libsource (lib "eagle-import") (part "CAPACITOR0603_CAP"))
    )
    (comp (ref "C49")
      (value "100n")
      (footprint "eagle-import:0603_CAP")
      (libsource (lib "eagle-import") (part "CAPACITOR0603_CAP"))
    )
    (comp (ref "D4")
      (value "LED-0805")
      (footprint "eagle-import:0805-DOT")
      (libsource (lib "eagle-import") (part "LED-0805"))
    )
    (comp (ref "D12")
      (value "LED-0805")
      (footprint "eagle-import:0805-DOT")
      (libsource (lib "eagle-import") (part "LED-0805"))
    )
    (comp (ref "D17")
      (value "LED-0805")
      (footprint "eagle-import:0805-DOT")
      (libsource (lib "eagle-import") (part "LED-0805"))
    )
    (comp (ref "D18")
      (value "LED-0805")
      (footprint "eagle-import:0805-DOT")
      (libsource (lib "eagle-import") (part "LED-0805"))
    )
    (comp (ref "D19")
      (value "LED-0805")
      (footprint "eagle-import:0805-DOT")
      (libsource (lib "eagle-import") (part "LED-0805"))
    )
    (comp (ref "D20")
      (value "LED-0805")
      (footprint "eagle-import:0805-DOT")
      (libsource (lib "eagle-import") (part "LED-0805"))
    )
    (comp (ref "R16")
      (value "10k")
      (footprint "eagle-import:0603-RES")
      (libsource (lib "eagle-import") (part "RESISTOR0603_RES"))
    )
    (comp (ref "R29")
      (value "10k")
      (footprint "eagle-import:0603-RES")
      (libsource (lib "eagle-import") (part "RESISTOR0603_RES"))
    )
    (comp (ref "R30")
      (value "10k")
      (footprint "eagle-import:0603-RES")
      (libsource (lib "eagle-import") (part "RESISTOR0603_RES"))
    )
    (comp (ref "R31")
      (value "10k")
      (footprint "eagle-import:0603-RES")
      (libsource (lib "eagle-import") (part "RESISTOR0603_RES"))
    )
    (comp (ref "R32")
      (value "10k")
      (footprint "eagle-import:0603-RES")
      (libsource (lib "eagle-import") (part "RESISTOR0603_RES"))
    )
    (comp (ref "R46")
      (value "1k")
      (footprint "eagle-import:0603-RES")
      (libsource (lib "eagle-import") (part "RESISTOR0603_RES"))
    )
    (comp (ref "R47")
      (value "1k")
      (footprint "eagle-import:0603-RES")
      (libsource (lib "eagle-import") (part "RESISTOR0603_RES"))
    )
    (comp (ref "R48")
      (value "1k")
      (footprint "eagle-import:0603-RES")
      (libsource (lib "eagle-import") (part "RESISTOR0603_RES"))
    )
    (comp (ref "R49")
      (value "1k")
      (footprint "eagle-import:0603-RES")
      (libsource (lib "eagle-import") (part "RESISTOR0603_RES"))
    )
    (comp (ref "R50")
      (value "1k")
      (footprint "eagle-import:0603-RES")
      (libsource (lib "eagle-import") (part "RESISTOR0603_RES"))
    )
    (comp (ref "R51")
      (value "1k")
      (footprint "eagle-import:0603-RES")
      (libsource (lib "eagle-import") (part "RESISTOR0603_RES"))
    )
    (comp (ref "S1")
      (value "SWITCH_2PD")
      (footprint "eagle-import:SWITCH_WH")
      (libsource (lib "eagle-import") (part "SWITCH_2PD"))
    )
    (comp (ref "U$1")
      (value "LOGO-TOBENG-1MM-FINISH")
      (footprint "eagle-import:TOBENG-1MM-FINISH")
      (libsource (lib "eagle-import") (part "LOGO-TOBENG-1MM-FINISH"))
    )
    (comp (ref "U1")
      (value "STM32F411VET6")
      (footprint "eagle-import:LQFP100-14X14MM")
      (fields (field (name "COPYRIGHT") "Copyright (C) 2018 Accelerated Designs. All rights reserved"))
      (libsource (lib "eagle-import") (part "STM32F411VET6"))
    )
    (comp (ref "V1")
      (value "FIDUCIAL2MM")
      (footprint "eagle-import:FIDUCIAL_2MM")
      (libsource (lib "eagle-import") (part "FIDUCIAL2MM"))
    )
    (comp (ref "V2")
      (value "FIDUCIAL2MM")
      (footprint "eagle-import:FIDUCIAL_2MM")
      (libsource (lib "eagle-import") (part "FIDUCIAL2MM"))
    )
    (comp (ref "V3")
      (value "FIDUCIAL2MM")
      (footprint "eagle-import:FIDUCIAL_2MM")
      (libsource (lib "eagle-import") (part "FIDUCIAL2MM"))
    )
    (comp (ref "V4")
      (value "FIDUCIAL2MM")
      (footprint "eagle-import:FIDUCIAL_2MM")
      (libsource (lib "eagle-import") (part "FIDUCIAL2MM"))
    )
    (comp (ref "X19")
      (value "05-JST-B5B-XH-A")
      (footprint "eagle-import:B5B-XH")
      (libsource (lib "eagle-import") (part "05-JST-B5B-XH-A"))
    )
    (comp (ref "X20")
      (value "05-JST-B5B-XH-A")
      (footprint "eagle-import:B5B-XH")
      (libsource (lib "eagle-import") (part "05-JST-B5B-XH-A"))
    )
    (comp (ref "X21")
      (value "04-JST-B4B-XH-A")
      (footprint "eagle-import:B4B-XH")
      (libsource (lib "eagle-import") (part "04-JST-B4B-XH-A"))
    )
    (comp (ref "X26")
      (value "05-JST-B5B-XH-A")
      (footprint "eagle-import:B5B-XH")
      (libsource (lib "eagle-import") (part "05-JST-B5B-XH-A"))
    )
    (comp (ref "X27")
      (value "05-JST-B5B-XH-A")
      (footprint "eagle-import:B5B-XH")
      (libsource (lib "eagle-import") (part "05-JST-B5B-XH-A"))
    )
    (comp (ref "X28")
      (value "05-JST-B5B-XH-A")
      (footprint "eagle-import:B5B-XH")
      (libsource (lib "eagle-import") (part "05-JST-B5B-XH-A"))
    )
    (comp (ref "Y1")
      (value "3213-QUARZ3225")
      (footprint "eagle-import:3225-QUARZ")
      (libsource (lib "eagle-import") (part "3213-QUARZ3225"))
    )
    (comp (ref "C4")
      (value "22p")
      (footprint "eagle-import:0603_CAP")
      (libsource (lib "eagle-import") (part "CAPACITOR0603_CAP"))
    )
    (comp (ref "C5")
      (value "100n")
      (footprint "eagle-import:0603_CAP")
      (libsource (lib "eagle-import") (part "CAPACITOR0603_CAP"))
    )
    (comp (ref "C16")
      (value "100n")
      (footprint "eagle-import:0603_CAP")
      (libsource (lib "eagle-import") (part "CAPACITOR0603_CAP"))
    )
    (comp (ref "C18")
      (value "22p")
      (footprint "eagle-import:0603_CAP")
      (libsource (lib "eagle-import") (part "CAPACITOR0603_CAP"))
    )
    (comp (ref "C19")
      (value "22p")
      (footprint "eagle-import:0603_CAP")
      (libsource (lib "eagle-import") (part "CAPACITOR0603_CAP"))
    )
    (comp (ref "C35")
      (value "10u")
      (footprint "eagle-import:0805_CAP")
      (libsource (lib "eagle-import") (part "CAPACITOR0805_CAP"))
    )
    (comp (ref "C36")
      (value "10u")
      (footprint "eagle-import:0805_CAP")
      (libsource (lib "eagle-import") (part "CAPACITOR0805_CAP"))
    )
    (comp (ref "C37")
      (value "100n")
      (footprint "eagle-import:0603_CAP")
      (libsource (lib "eagle-import") (part "CAPACITOR0603_CAP"))
    )
    (comp (ref "C38")
      (value "100n")
      (footprint "eagle-import:0603_CAP")
      (libsource (lib "eagle-import") (part "CAPACITOR0603_CAP"))
    )
    (comp (ref "C39")
      (value "10u")
      (footprint "eagle-import:0805_CAP")
      (libsource (lib "eagle-import") (part "CAPACITOR0805_CAP"))
    )
    (comp (ref "C40")
      (value "100n")
      (footprint "eagle-import:0603_CAP")
      (libsource (lib "eagle-import") (part "CAPACITOR0603_CAP"))
    )
    (comp (ref "C41")
      (value "22p")
      (footprint "eagle-import:0603_CAP")
      (libsource (lib "eagle-import") (part "CAPACITOR0603_CAP"))
    )
    (comp (ref "C42")
      (value "100n")
      (footprint "eagle-import:0603_CAP")
      (libsource (lib "eagle-import") (part "CAPACITOR0603_CAP"))
    )
    (comp (ref "D10")
      (value "DIODE-1206")
      (footprint "eagle-import:1206-DOT")
      (libsource (lib "eagle-import") (part "DIODE-1206"))
    )
    (comp (ref "D16")
      (value "DIODE-TVS")
      (footprint "eagle-import:SOT-23")
      (libsource (lib "eagle-import") (part "DIODE-TVS"))
    )
    (comp (ref "F1")
      (value "PTCFUSE-1206")
      (footprint "eagle-import:R1206")
      (libsource (lib "eagle-import") (part "PTCFUSE-1206"))
    )
    (comp (ref "J1")
      (value "USB-ID-THT")
      (footprint "eagle-import:USB-MICRO-THT")
      (libsource (lib "eagle-import") (part "USB-ID-THT"))
    )
    (comp (ref "J3")
      (value "USB-LCSC_C42431")
      (footprint "eagle-import:USB-A-LCSC_C42431")
      (libsource (lib "eagle-import") (part "USB-LCSC_C42431"))
    )
    (comp (ref "J3C")
      (value "USB-LCSC_C42431")
      (footprint "eagle-import:USB-A-LCSC_C42431")
      (libsource (lib "eagle-import") (part "USB-LCSC_C42431"))
    )
    (comp (ref "J3C1")
      (value "USB-LCSC_C42431")
      (footprint "eagle-import:USB-A-LCSC_C42431")
      (libsource (lib "eagle-import") (part "USB-LCSC_C42431"))
    )
    (comp (ref "R1")
      (value "1k")
      (footprint "eagle-import:0603-RES")
      (libsource (lib "eagle-import") (part "RESISTOR0603_RES"))
    )
    (comp (ref "R2")
      (value "1k")
      (footprint "eagle-import:0603-RES")
      (libsource (lib "eagle-import") (part "RESISTOR0603_RES"))
    )
    (comp (ref "R3")
      (value "1k")
      (footprint "eagle-import:0603-RES")
      (libsource (lib "eagle-import") (part "RESISTOR0603_RES"))
    )
    (comp (ref "U2")
      (value "CH340")
      (footprint "eagle-import:SOIC-16")
      (libsource (lib "eagle-import") (part "CH340"))
    )
    (comp (ref "U4")
      (value "SL2.1A")
      (footprint "eagle-import:SOIC-16")
      (libsource (lib "eagle-import") (part "SL2.1A"))
    )
    (comp (ref "Y2")
      (value "3213-QUARZ3225")
      (footprint "eagle-import:3225-QUARZ")
      (libsource (lib "eagle-import") (part "3213-QUARZ3225"))
    )
    (comp (ref "Y3")
      (value "3213-QUARZ3225")
      (footprint "eagle-import:3225-QUARZ")
      (libsource (lib "eagle-import") (part "3213-QUARZ3225"))
    )
    (comp (ref "C7")
      (value "CAPACITOR0603_CAP")
      (footprint "eagle-import:0603_CAP")
      (libsource (lib "eagle-import") (part "CAPACITOR0603_CAP"))
    )
    (comp (ref "C8")
      (value "CAPACITOR0603_CAP")
      (footprint "eagle-import:0603_CAP")
      (libsource (lib "eagle-import") (part "CAPACITOR0603_CAP"))
    )
    (comp (ref "C9")
      (value "CPOL-EU175TMP-0808")
      (footprint "eagle-import:175TMP-0808")
      (libsource (lib "eagle-import") (part "CPOL-EU175TMP-0808"))
    )
    (comp (ref "C10")
      (value "CAPACITOR0603_CAP")
      (footprint "eagle-import:0603_CAP")
      (libsource (lib "eagle-import") (part "CAPACITOR0603_CAP"))
    )
    (comp (ref "C11")
      (value "CPOL-EU175TMP-0808")
      (footprint "eagle-import:175TMP-0808")
      (libsource (lib "eagle-import") (part "CPOL-EU175TMP-0808"))
    )
    (comp (ref "C12")
      (value "CAPACITOR0603_CAP")
      (footprint "eagle-import:0603_CAP")
      (libsource (lib "eagle-import") (part "CAPACITOR0603_CAP"))
    )
    (comp (ref "C13")
      (value "CPOL-EU175TMP-0808")
      (footprint "eagle-import:175TMP-0808")
      (libsource (lib "eagle-import") (part "CPOL-EU175TMP-0808"))
    )
    (comp (ref "C14")
      (value "CAPACITOR0603_CAP")
      (footprint "eagle-import:0603_CAP")
      (libsource (lib "eagle-import") (part "CAPACITOR0603_CAP"))
    )
    (comp (ref "C15")
      (value "CPOL-EU175TMP-0808")
      (footprint "eagle-import:175TMP-0808")
      (libsource (lib "eagle-import") (part "CPOL-EU175TMP-0808"))
    )
    (comp (ref "C17")
      (value "CAPACITOR0603_CAP")
      (footprint "eagle-import:0603_CAP")
      (libsource (lib "eagle-import") (part "CAPACITOR0603_CAP"))
    )
    (comp (ref "C20")
      (value "CPOL-EU175TMP-0808")
      (footprint "eagle-import:175TMP-0808")
      (libsource (lib "eagle-import") (part "CPOL-EU175TMP-0808"))
    )
    (comp (ref "C21")
      (value "CAPACITOR0603_CAP")
      (footprint "eagle-import:0603_CAP")
      (libsource (lib "eagle-import") (part "CAPACITOR0603_CAP"))
    )
    (comp (ref "C22")
      (value "CPOL-EU175TMP-0808")
      (footprint "eagle-import:175TMP-0808")
      (libsource (lib "eagle-import") (part "CPOL-EU175TMP-0808"))
    )
    (comp (ref "C32")
      (value "CPOL-EU175TMP-0808")
      (footprint "eagle-import:175TMP-0808")
      (libsource (lib "eagle-import") (part "CPOL-EU175TMP-0808"))
    )
    (comp (ref "C33")
      (value "CAPACITOR0603_CAP")
      (footprint "eagle-import:0603_CAP")
      (libsource (lib "eagle-import") (part "CAPACITOR0603_CAP"))
    )
    (comp (ref "C34")
      (value "CPOL-EU175TMP-0808")
      (footprint "eagle-import:175TMP-0808")
      (libsource (lib "eagle-import") (part "CPOL-EU175TMP-0808"))
    )
    (comp (ref "U$2")
      (value "A4988BREAKOUT")
      (footprint "eagle-import:A4988BREAKOUT")
      (libsource (lib "eagle-import") (part "A4988BREAKOUT"))
    )
    (comp (ref "U$3")
      (value "A4988BREAKOUT")
      (footprint "eagle-import:A4988BREAKOUT")
      (libsource (lib "eagle-import") (part "A4988BREAKOUT"))
    )
    (comp (ref "U$4")
      (value "A4988BREAKOUT")
      (footprint "eagle-import:A4988BREAKOUT")
      (libsource (lib "eagle-import") (part "A4988BREAKOUT"))
    )
    (comp (ref "U$5")
      (value "A4988BREAKOUT")
      (footprint "eagle-import:A4988BREAKOUT")
      (libsource (lib "eagle-import") (part "A4988BREAKOUT"))
    )
    (comp (ref "U$6")
      (value "A4988BREAKOUT")
      (footprint "eagle-import:A4988BREAKOUT")
      (libsource (lib "eagle-import") (part "A4988BREAKOUT"))
    )
    (comp (ref "U$7")
      (value "A4988BREAKOUT")
      (footprint "eagle-import:A4988BREAKOUT")
      (libsource (lib "eagle-import") (part "A4988BREAKOUT"))
    )
    (comp (ref "U$8")
      (value "A4988BREAKOUT")
      (footprint "eagle-import:A4988BREAKOUT")
      (libsource (lib "eagle-import") (part "A4988BREAKOUT"))
    )
    (comp (ref "U$9")
      (value "A4988BREAKOUT")
      (footprint "eagle-import:A4988BREAKOUT")
      (libsource (lib "eagle-import") (part "A4988BREAKOUT"))
    )
    (comp (ref "X1")
      (value "04-JST-B4B-XH-A")
      (footprint "eagle-import:B4B-XH")
      (libsource (lib "eagle-import") (part "04-JST-B4B-XH-A"))
    )
    (comp (ref "X2")
      (value "04-JST-B4B-XH-A")
      (footprint "eagle-import:B4B-XH")
      (libsource (lib "eagle-import") (part "04-JST-B4B-XH-A"))
    )
    (comp (ref "X3")
      (value "04-JST-B4B-XH-A")
      (footprint "eagle-import:B4B-XH")
      (libsource (lib "eagle-import") (part "04-JST-B4B-XH-A"))
    )
    (comp (ref "X4")
      (value "04-JST-B4B-XH-A")
      (footprint "eagle-import:B4B-XH")
      (libsource (lib "eagle-import") (part "04-JST-B4B-XH-A"))
    )
    (comp (ref "X5")
      (value "04-JST-B4B-XH-A")
      (footprint "eagle-import:B4B-XH")
      (libsource (lib "eagle-import") (part "04-JST-B4B-XH-A"))
    )
    (comp (ref "X6")
      (value "04-JST-B4B-XH-A")
      (footprint "eagle-import:B4B-XH")
      (libsource (lib "eagle-import") (part "04-JST-B4B-XH-A"))
    )
    (comp (ref "X25")
      (value "04-JST-B4B-XH-A")
      (footprint "eagle-import:B4B-XH")
      (libsource (lib "eagle-import") (part "04-JST-B4B-XH-A"))
    )
    (comp (ref "X33")
      (value "04-JST-B4B-XH-A")
      (footprint "eagle-import:B4B-XH")
      (libsource (lib "eagle-import") (part "04-JST-B4B-XH-A"))
    )
  )
  (nets
    (net (code "1") (name "+3V3") (class "Default")
      (node (ref "C10") (pin "1") (pinfunction "1_1") (pintype "bidirectional"))
      (node (ref "C12") (pin "1") (pinfunction "1_1") (pintype "bidirectional"))
      (node (ref "C14") (pin "1") (pinfunction "1_1") (pintype "bidirectional"))
      (node (ref "C17") (pin "1") (pinfunction "1_1") (pintype "bidirectional"))
      (node (ref "C2") (pin "1") (pinfunction "1_1") (pintype "bidirectional"))
      (node (ref "C21") (pin "1") (pinfunction "1_1") (pintype "bidirectional"))
      (node (ref "C3") (pin "1") (pinfunction "1_1") (pintype "bidirectional"))
      (node (ref "C33") (pin "1") (pinfunction "1_1") (pintype "bidirectional"))
      (node (ref "C44") (pin "1") (pinfunction "1_1") (pintype "bidirectional"))
      (node (ref "C45") (pin "1") (pinfunction "1_1") (pintype "bidirectional"))
      (node (ref "C46") (pin "1") (pinfunction "1_1") (pintype "bidirectional"))
      (node (ref "C47") (pin "P$1") (pinfunction "1_P$1") (pintype "bidirectional"))
      (node (ref "C48") (pin "1") (pinfunction "1_1") (pintype "bidirectional"))
      (node (ref "C49") (pin "1") (pinfunction "1_1") (pintype "bidirectional"))
      (node (ref "C58") (pin "1") (pinfunction "1_1") (pintype "bidirectional"))
      (node (ref "C6") (pin "1") (pinfunction "1_1") (pintype "bidirectional"))
      (node (ref "C62") (pin "P$1") (pinfunction "1_P$1") (pintype "bidirectional"))
      (node (ref "C63") (pin "P$1") (pinfunction "1_P$1") (pintype "bidirectional"))
      (node (ref "C7") (pin "1") (pinfunction "1_1") (pintype "bidirectional"))
      (node (ref "C8") (pin "1") (pinfunction "1_1") (pintype "bidirectional"))
      (node (ref "D19") (pin "1") (pinfunction "1_1") (pintype "bidirectional"))
      (node (ref "D20") (pin "1") (pinfunction "1_1") (pintype "bidirectional"))
      (node (ref "L2") (pin "P$2") (pinfunction "2_P$2") (pintype "passive"))
      (node (ref "R11") (pin "1") (pinfunction "1_1") (pintype "passive"))
      (node (ref "R13") (pin "1") (pinfunction "1_1") (pintype "passive"))
      (node (ref "R15") (pin "1") (pinfunction "1_1") (pintype "passive"))
      (node (ref "R16") (pin "1") (pinfunction "1_1") (pintype "passive"))
      (node (ref "R29") (pin "1") (pinfunction "1_1") (pintype "passive"))
      (node (ref "R31") (pin "1") (pinfunction "1_1") (pintype "passive"))
      (node (ref "R32") (pin "1") (pinfunction "1_1") (pintype "passive"))
      (node (ref "R37") (pin "2") (pinfunction "2_2") (pintype "passive"))
      (node (ref "R4") (pin "1") (pinfunction "1_1") (pintype "passive"))
      (node (ref "R7") (pin "1") (pinfunction "1_1") (pintype "passive"))
      (node (ref "R9") (pin "1") (pinfunction "1_1") (pintype "passive"))
      (node (ref "U$2") (pin "VDD") (pinfunction "VDD_VDD") (pintype "power_in"))
      (node (ref "U$3") (pin "VDD") (pinfunction "VDD_VDD") (pintype "power_in"))
      (node (ref "U$4") (pin "VDD") (pinfunction "VDD_VDD") (pintype "power_in"))
      (node (ref "U$5") (pin "VDD") (pinfunction "VDD_VDD") (pintype "power_in"))
      (node (ref "U$6") (pin "VDD") (pinfunction "VDD_VDD") (pintype "power_in"))
      (node (ref "U$7") (pin "VDD") (pinfunction "VDD_VDD") (pintype "power_in"))
      (node (ref "U$8") (pin "VDD") (pinfunction "VDD_VDD") (pintype "power_in"))
      (node (ref "U$9") (pin "VDD") (pinfunction "VDD_VDD") (pintype "power_in"))
      (node (ref "U1") (pin "100") (pinfunction "VDD_100") (pintype "power_in"))
      (node (ref "U1") (pin "11") (pinfunction "VDD_2_11") (pintype "power_in"))
      (node (ref "U1") (pin "19") (pinfunction "VDD_3_19") (pintype "power_in"))
      (node (ref "U1") (pin "21") (pinfunction "VREF+_21") (pintype "power_in"))
      (node (ref "U1") (pin "22") (pinfunction "VDDA_22") (pintype "power_in"))
      (node (ref "U1") (pin "28") (pinfunction "VDD_4_28") (pintype "power_in"))
      (node (ref "U1") (pin "50") (pinfunction "VDD_5_50") (pintype "power_in"))
      (node (ref "U1") (pin "6") (pinfunction "VBAT_6") (pintype "power_in"))
      (node (ref "U1") (pin "75") (pinfunction "VDD_6_75") (pintype "power_in"))
      (node (ref "X10") (pin "P$3") (pinfunction "1_P$3") (pintype "passive"))
      (node (ref "X11") (pin "P$3") (pinfunction "1_P$3") (pintype "passive"))
      (node (ref "X12") (pin "P$3") (pinfunction "1_P$3") (pintype "passive"))
      (node (ref "X26") (pin "P$1") (pinfunction "1_P$1") (pintype "passive"))
      (node (ref "X29") (pin "P$2") (pinfunction "1_P$2") (pintype "passive"))
      (node (ref "X30") (pin "P$2") (pinfunction "1_P$2") (pintype "passive"))
      (node (ref "X7") (pin "P$3") (pinfunction "1_P$3") (pintype "passive"))
      (node (ref "X8") (pin "P$3") (pinfunction "1_P$3") (pintype "passive"))
      (node (ref "X9") (pin "P$3") (pinfunction "1_P$3") (pintype "passive"))
    )
    (net (code "2") (name "+5V") (class "Default")
      (node (ref "C35") (pin "P$2") (pinfunction "2_P$2") (pintype "bidirectional"))
      (node (ref "C37") (pin "1") (pinfunction "1_1") (pintype "bidirectional"))
      (node (ref "C38") (pin "1") (pinfunction "1_1") (pintype "bidirectional"))
      (node (ref "C40") (pin "2") (pinfunction "2_2") (pintype "bidirectional"))
      (node (ref "C42") (pin "1") (pinfunction "1_1") (pintype "bidirectional"))
      (node (ref "C5") (pin "2") (pinfunction "2_2") (pintype "bidirectional"))
      (node (ref "C51") (pin "1") (pinfunction "1_1") (pintype "bidirectional"))
      (node (ref "C55") (pin "P$1") (pinfunction "1_P$1") (pintype "bidirectional"))
      (node (ref "C56") (pin "P$1") (pinfunction "1_P$1") (pintype "bidirectional"))
      (node (ref "D10") (pin "2") (pinfunction "2_2") (pintype "bidirectional"))
      (node (ref "D2") (pin "K") (pinfunction "CATHODE_K") (pintype "bidirectional"))
      (node (ref "D3") (pin "1") (pinfunction "1_1") (pintype "bidirectional"))
      (node (ref "J3") (pin "VCC") (pinfunction "VCC_VCC") (pintype "bidirectional"))
      (node (ref "J3C") (pin "VCC") (pinfunction "VCC_VCC") (pintype "bidirectional"))
      (node (ref "J3C1") (pin "VCC") (pinfunction "VCC_VCC") (pintype "bidirectional"))
      (node (ref "L1") (pin "P$2") (pinfunction "2_P$2") (pintype "passive"))
      (node (ref "R34") (pin "2") (pinfunction "2_2") (pintype "passive"))
      (node (ref "U2") (pin "16") (pinfunction "VCC_16") (pintype "bidirectional"))
      (node (ref "U4") (pin "11") (pinfunction "VCC5V_11") (pintype "bidirectional"))
      (node (ref "X14") (pin "P$2") (pinfunction "1_P$2") (pintype "passive"))
      (node (ref "X19") (pin "P$4") (pinfunction "1_P$4") (pintype "passive"))
      (node (ref "X20") (pin "P$4") (pinfunction "1_P$4") (pintype "passive"))
      (node (ref "X31") (pin "P$2") (pinfunction "1_P$2") (pintype "passive"))
      (node (ref "X32") (pin "P$2") (pinfunction "1_P$2") (pintype "passive"))
    )
    (net (code "3") (name "+12V") (class "Default")
      (node (ref "C11") (pin "+") (pinfunction "+_+") (pintype "passive"))
      (node (ref "C13") (pin "+") (pinfunction "+_+") (pintype "passive"))
      (node (ref "C15") (pin "+") (pinfunction "+_+") (pintype "passive"))
      (node (ref "C20") (pin "+") (pinfunction "+_+") (pintype "passive"))
      (node (ref "C22") (pin "+") (pinfunction "+_+") (pintype "passive"))
      (node (ref "C32") (pin "+") (pinfunction "+_+") (pintype "passive"))
      (node (ref "C34") (pin "+") (pinfunction "+_+") (pintype "passive"))
      (node (ref "C54") (pin "1") (pinfunction "1_1") (pintype "bidirectional"))
      (node (ref "C61") (pin "1") (pinfunction "1_1") (pintype "bidirectional"))
      (node (ref "C9") (pin "+") (pinfunction "+_+") (pintype "passive"))
      (node (ref "D1") (pin "1") (pinfunction "1_1") (pintype "bidirectional"))
      (node (ref "D11") (pin "1") (pinfunction "1_1") (pintype "bidirectional"))
      (node (ref "D13") (pin "K") (pinfunction "CATHODE_K") (pintype "bidirectional"))
      (node (ref "D14") (pin "K") (pinfunction "CATHODE_K") (pintype "bidirectional"))
      (node (ref "D15") (pin "1") (pinfunction "1_1") (pintype "bidirectional"))
      (node (ref "D5") (pin "K") (pinfunction "CATHODE_K") (pintype "bidirectional"))
      (node (ref "D6") (pin "1") (pinfunction "1_1") (pintype "bidirectional"))
      (node (ref "D7") (pin "K") (pinfunction "CATHODE_K") (pintype "bidirectional"))
      (node (ref "D8") (pin "1") (pinfunction "1_1") (pintype "bidirectional"))
      (node (ref "D9") (pin "K") (pinfunction "CATHODE_K") (pintype "bidirectional"))
      (node (ref "R33") (pin "1") (pinfunction "1_1") (pintype "passive"))
      (node (ref "R36") (pin "1") (pinfunction "1_1") (pintype "passive"))
      (node (ref "U$2") (pin "VMOT") (pinfunction "VMOT_VMOT") (pintype "power_in"))
      (node (ref "U$3") (pin "VMOT") (pinfunction "VMOT_VMOT") (pintype "power_in"))
      (node (ref "U$4") (pin "VMOT") (pinfunction "VMOT_VMOT") (pintype "power_in"))
      (node (ref "U$5") (pin "VMOT") (pinfunction "VMOT_VMOT") (pintype "power_in"))
      (node (ref "U$6") (pin "VMOT") (pinfunction "VMOT_VMOT") (pintype "power_in"))
      (node (ref "U$7") (pin "VMOT") (pinfunction "VMOT_VMOT") (pintype "power_in"))
      (node (ref "U$8") (pin "VMOT") (pinfunction "VMOT_VMOT") (pintype "power_in"))
      (node (ref "U$9") (pin "VMOT") (pinfunction "VMOT_VMOT") (pintype "power_in"))
      (node (ref "U3") (pin "8") (pinfunction "VIN_8") (pintype "input"))
      (node (ref "U5") (pin "8") (pinfunction "VIN_8") (pintype "input"))
      (node (ref "X13") (pin "P$2") (pinfunction "1_P$2") (pintype "passive"))
      (node (ref "X15") (pin "P$2") (pinfunction "1_P$2") (pintype "passive"))
      (node (ref "X16") (pin "P$2") (pinfunction "1_P$2") (pintype "passive"))
      (node (ref "X17") (pin "P$2") (pinfunction "1_P$2") (pintype "passive"))
      (node (ref "X18") (pin "P$2") (pinfunction "1_P$2") (pintype "passive"))
      (node (ref "X22") (pin "1") (pinfunction "1_1") (pintype "bidirectional"))
      (node (ref "X23") (pin "P$2") (pinfunction "1_P$2") (pintype "passive"))
      (node (ref "X24") (pin "P$2") (pinfunction "1_P$2") (pintype "passive"))
    )
    (net (code "4") (name "D0_N") (class "Default")
      (node (ref "D16") (pin "2") (pinfunction "2_2") (pintype "bidirectional"))
      (node (ref "J1") (pin "2") (pinfunction "D-_2") (pintype "bidirectional"))
      (node (ref "U4") (pin "9") (pinfunction "UDM_9") (pintype "bidirectional"))
    )
    (net (code "5") (name "D0_P") (class "Default")
      (node (ref "D16") (pin "1") (pinfunction "1_1") (pintype "bidirectional"))
      (node (ref "J1") (pin "3") (pinfunction "D+_3") (pintype "bidirectional"))
      (node (ref "U4") (pin "10") (pinfunction "UDP_10") (pintype "bidirectional"))
    )
    (net (code "6") (name "D1_N") (class "Default")
      (node (ref "U2") (pin "6") (pinfunction "UD-_6") (pintype "bidirectional"))
      (node (ref "U4") (pin "7") (pinfunction "DM1_7") (pintype "bidirectional"))
    )
    (net (code "7") (name "D1_P") (class "Default")
      (node (ref "U2") (pin "5") (pinfunction "UD+_5") (pintype "bidirectional"))
      (node (ref "U4") (pin "8") (pinfunction "DP1_8") (pintype "bidirectional"))
    )
    (net (code "8") (name "D2_N") (class "Default")
      (node (ref "J3") (pin "D-") (pinfunction "D-_D-") (pintype "bidirectional"))
      (node (ref "U4") (pin "5") (pinfunction "DM2_5") (pintype "bidirectional"))
    )
    (net (code "9") (name "D2_P") (class "Default")
      (node (ref "J3") (pin "D+") (pinfunction "D+_D+") (pintype "bidirectional"))
      (node (ref "U4") (pin "6") (pinfunction "DP2_6") (pintype "bidirectional"))
    )
    (net (code "10") (name "D3_N") (class "Default")
      (node (ref "J3C") (pin "D-") (pinfunction "D-_D-") (pintype "bidirectional"))
      (node (ref "U4") (pin "3") (pinfunction "DM3_3") (pintype "bidirectional"))
    )
    (net (code "11") (name "D3_P") (class "Default")
      (node (ref "J3C") (pin "D+") (pinfunction "D+_D+") (pintype "bidirectional"))
      (node (ref "U4") (pin "4") (pinfunction "DP3_4") (pintype "bidirectional"))
    )
    (net (code "12") (name "D4_N") (class "Default")
      (node (ref "J3C1") (pin "D-") (pinfunction "D-_D-") (pintype "bidirectional"))
      (node (ref "U4") (pin "1") (pinfunction "DM4_1") (pintype "bidirectional"))
    )
    (net (code "13") (name "D4_P") (class "Default")
      (node (ref "J3C1") (pin "D+") (pinfunction "D+_D+") (pintype "bidirectional"))
      (node (ref "U4") (pin "2") (pinfunction "DP4_2") (pintype "bidirectional"))
    )
    (net (code "14") (name "DTR") (class "Default")
      (node (ref "R3") (pin "2") (pinfunction "2_2") (pintype "passive"))
      (node (ref "U1") (pin "70") (pinfunction "PA11_70") (pintype "bidirectional"))
    )
    (net (code "15") (name "GND") (class "Default")
      (node (ref "C1") (pin "P$2") (pinfunction "2_P$2") (pintype "bidirectional"))
      (node (ref "C10") (pin "2") (pinfunction "2_2") (pintype "bidirectional"))
      (node (ref "C11") (pin "-") (pinfunction "-_-") (pintype "passive"))
      (node (ref "C12") (pin "2") (pinfunction "2_2") (pintype "bidirectional"))
      (node (ref "C13") (pin "-") (pinfunction "-_-") (pintype "passive"))
      (node (ref "C14") (pin "2") (pinfunction "2_2") (pintype "bidirectional"))
      (node (ref "C15") (pin "-") (pinfunction "-_-") (pintype "passive"))
      (node (ref "C16") (pin "1") (pinfunction "1_1") (pintype "bidirectional"))
      (node (ref "C17") (pin "2") (pinfunction "2_2") (pintype "bidirectional"))
      (node (ref "C18") (pin "1") (pinfunction "1_1") (pintype "bidirectional"))
      (node (ref "C19") (pin "1") (pinfunction "1_1") (pintype "bidirectional"))
      (node (ref "C2") (pin "2") (pinfunction "2_2") (pintype "bidirectional"))
      (node (ref "C20") (pin "-") (pinfunction "-_-") (pintype "passive"))
      (node (ref "C21") (pin "2") (pinfunction "2_2") (pintype "bidirectional"))
      (node (ref "C22") (pin "-") (pinfunction "-_-") (pintype "passive"))
      (node (ref "C23") (pin "2") (pinfunction "2_2") (pintype "bidirectional"))
      (node (ref "C24") (pin "2") (pinfunction "2_2") (pintype "bidirectional"))
      (node (ref "C25") (pin "2") (pinfunction "2_2") (pintype "bidirectional"))
      (node (ref "C26") (pin "2") (pinfunction "2_2") (pintype "bidirectional"))
      (node (ref "C27") (pin "2") (pinfunction "2_2") (pintype "bidirectional"))
      (node (ref "C28") (pin "2") (pinfunction "2_2") (pintype "bidirectional"))
      (node (ref "C29") (pin "2") (pinfunction "2_2") (pintype "bidirectional"))
      (node (ref "C3") (pin "2") (pinfunction "2_2") (pintype "bidirectional"))
      (node (ref "C30") (pin "2") (pinfunction "2_2") (pintype "bidirectional"))
      (node (ref "C31") (pin "2") (pinfunction "2_2") (pintype "bidirectional"))
      (node (ref "C32") (pin "-") (pinfunction "-_-") (pintype "passive"))
      (node (ref "C33") (pin "2") (pinfunction "2_2") (pintype "bidirectional"))
      (node (ref "C34") (pin "-") (pinfunction "-_-") (pintype "passive"))
      (node (ref "C35") (pin "P$1") (pinfunction "1_P$1") (pintype "bidirectional"))
      (node (ref "C36") (pin "P$1") (pinfunction "1_P$1") (pintype "bidirectional"))
      (node (ref "C37") (pin "2") (pinfunction "2_2") (pintype "bidirectional"))
      (node (ref "C38") (pin "2") (pinfunction "2_2") (pintype "bidirectional"))
      (node (ref "C39") (pin "P$1") (pinfunction "1_P$1") (pintype "bidirectional"))
      (node (ref "C4") (pin "2") (pinfunction "2_2") (pintype "bidirectional"))
      (node (ref "C40") (pin "1") (pinfunction "1_1") (pintype "bidirectional"))
      (node (ref "C41") (pin "2") (pinfunction "2_2") (pintype "bidirectional"))
      (node (ref "C42") (pin "2") (pinfunction "2_2") (pintype "bidirectional"))
      (node (ref "C43") (pin "2") (pinfunction "2_2") (pintype "bidirectional"))
      (node (ref "C44") (pin "2") (pinfunction "2_2") (pintype "bidirectional"))
      (node (ref "C45") (pin "2") (pinfunction "2_2") (pintype "bidirectional"))
      (node (ref "C46") (pin "2") (pinfunction "2_2") (pintype "bidirectional"))
      (node (ref "C47") (pin "P$2") (pinfunction "2_P$2") (pintype "bidirectional"))
      (node (ref "C48") (pin "2") (pinfunction "2_2") (pintype "bidirectional"))
      (node (ref "C49") (pin "2") (pinfunction "2_2") (pintype "bidirectional"))
      (node (ref "C5") (pin "1") (pinfunction "1_1") (pintype "bidirectional"))
      (node (ref "C52") (pin "2") (pinfunction "2_2") (pintype "bidirectional"))
      (node (ref "C53") (pin "2") (pinfunction "2_2") (pintype "bidirectional"))
      (node (ref "C54") (pin "2") (pinfunction "2_2") (pintype "bidirectional"))
      (node (ref "C55") (pin "P$2") (pinfunction "2_P$2") (pintype "bidirectional"))
      (node (ref "C56") (pin "P$2") (pinfunction "2_P$2") (pintype "bidirectional"))
      (node (ref "C59") (pin "2") (pinfunction "2_2") (pintype "bidirectional"))
      (node (ref "C6") (pin "2") (pinfunction "2_2") (pintype "bidirectional"))
      (node (ref "C60") (pin "2") (pinfunction "2_2") (pintype "bidirectional"))
      (node (ref "C61") (pin "2") (pinfunction "2_2") (pintype "bidirectional"))
      (node (ref "C62") (pin "P$2") (pinfunction "2_P$2") (pintype "bidirectional"))
      (node (ref "C63") (pin "P$2") (pinfunction "2_P$2") (pintype "bidirectional"))
      (node (ref "C7") (pin "2") (pinfunction "2_2") (pintype "bidirectional"))
      (node (ref "C8") (pin "2") (pinfunction "2_2") (pintype "bidirectional"))
      (node (ref "C9") (pin "-") (pinfunction "-_-") (pintype "passive"))
      (node (ref "D16") (pin "3") (pinfunction "3_3") (pintype "bidirectional"))
      (node (ref "J1") (pin "5") (pinfunction "GND_5") (pintype "bidirectional"))
      (node (ref "J1") (pin "GND1") (pinfunction "GND_GND1") (pintype "bidirectional"))
      (node (ref "J1") (pin "GND2") (pinfunction "GND_GND2") (pintype "bidirectional"))
      (node (ref "J1") (pin "GND3") (pinfunction "GND_GND3") (pintype "bidirectional"))
      (node (ref "J1") (pin "GND4") (pinfunction "GND_GND4") (pintype "bidirectional"))
      (node (ref "J3") (pin "COM1") (pinfunction "COM_COM1") (pintype "bidirectional"))
      (node (ref "J3") (pin "COM2") (pinfunction "COM_COM2") (pintype "bidirectional"))
      (node (ref "J3") (pin "GND") (pinfunction "GND_GND") (pintype "bidirectional"))
      (node (ref "J3C") (pin "COM1") (pinfunction "COM_COM1") (pintype "bidirectional"))
      (node (ref "J3C") (pin "COM2") (pinfunction "COM_COM2") (pintype "bidirectional"))
      (node (ref "J3C") (pin "GND") (pinfunction "GND_GND") (pintype "bidirectional"))
      (node (ref "J3C1") (pin "COM1") (pinfunction "COM_COM1") (pintype "bidirectional"))
      (node (ref "J3C1") (pin "COM2") (pinfunction "COM_COM2") (pintype "bidirectional"))
      (node (ref "J3C1") (pin "GND") (pinfunction "GND_GND") (pintype "bidirectional"))
      (node (ref "R17") (pin "1") (pinfunction "1_1") (pintype "passive"))
      (node (ref "R19") (pin "1") (pinfunction "1_1") (pintype "passive"))
      (node (ref "R21") (pin "1") (pinfunction "1_1") (pintype "passive"))
      (node (ref "R23") (pin "1") (pinfunction "1_1") (pintype "passive"))
      (node (ref "R25") (pin "1") (pinfunction "1_1") (pintype "passive"))
      (node (ref "R27") (pin "1") (pinfunction "1_1") (pintype "passive"))
      (node (ref "R30") (pin "2") (pinfunction "2_2") (pintype "passive"))
      (node (ref "R35") (pin "1") (pinfunction "1_1") (pintype "passive"))
      (node (ref "R39") (pin "2") (pinfunction "2_2") (pintype "passive"))
      (node (ref "R46") (pin "1") (pinfunction "1_1") (pintype "passive"))
      (node (ref "R47") (pin "1") (pinfunction "1_1") (pintype "passive"))
      (node (ref "R48") (pin "1") (pinfunction "1_1") (pintype "passive"))
      (node (ref "R49") (pin "1") (pinfunction "1_1") (pintype "passive"))
      (node (ref "S1") (pin "2A") (pinfunction "3_2A") (pintype "bidirectional"))
      (node (ref "S1") (pin "2B") (pinfunction "4_2B") (pintype "bidirectional"))
      (node (ref "U$2") (pin "GND") (pinfunction "GND_GND") (pintype "power_in"))
      (node (ref "U$2") (pin "GND@0") (pinfunction "GND_GND@0") (pintype "power_in"))
      (node (ref "U$21") (pin "S1") (pinfunction "S_S1") (pintype "bidirectional"))
      (node (ref "U$21") (pin "S2") (pinfunction "S_S2") (pintype "bidirectional"))
      (node (ref "U$21") (pin "S3") (pinfunction "S_S3") (pintype "bidirectional"))
      (node (ref "U$22") (pin "S1") (pinfunction "S_S1") (pintype "bidirectional"))
      (node (ref "U$22") (pin "S2") (pinfunction "S_S2") (pintype "bidirectional"))
      (node (ref "U$22") (pin "S3") (pinfunction "S_S3") (pintype "bidirectional"))
      (node (ref "U$23") (pin "S1") (pinfunction "S_S1") (pintype "bidirectional"))
      (node (ref "U$23") (pin "S2") (pinfunction "S_S2") (pintype "bidirectional"))
      (node (ref "U$23") (pin "S3") (pinfunction "S_S3") (pintype "bidirectional"))
      (node (ref "U$24") (pin "S1") (pinfunction "S_S1") (pintype "bidirectional"))
      (node (ref "U$24") (pin "S2") (pinfunction "S_S2") (pintype "bidirectional"))
      (node (ref "U$24") (pin "S3") (pinfunction "S_S3") (pintype "bidirectional"))
      (node (ref "U$25") (pin "S1") (pinfunction "S_S1") (pintype "bidirectional"))
      (node (ref "U$25") (pin "S2") (pinfunction "S_S2") (pintype "bidirectional"))
      (node (ref "U$25") (pin "S3") (pinfunction "S_S3") (pintype "bidirectional"))
      (node (ref "U$26") (pin "S1") (pinfunction "S_S1") (pintype "bidirectional"))
      (node (ref "U$26") (pin "S2") (pinfunction "S_S2") (pintype "bidirectional"))
      (node (ref "U$26") (pin "S3") (pinfunction "S_S3") (pintype "bidirectional"))
      (node (ref "U$3") (pin "GND") (pinfunction "GND_GND") (pintype "power_in"))
      (node (ref "U$3") (pin "GND@0") (pinfunction "GND_GND@0") (pintype "power_in"))
      (node (ref "U$4") (pin "GND") (pinfunction "GND_GND") (pintype "power_in"))
      (node (ref "U$4") (pin "GND@0") (pinfunction "GND_GND@0") (pintype "power_in"))
      (node (ref "U$5") (pin "GND") (pinfunction "GND_GND") (pintype "power_in"))
      (node (ref "U$5") (pin "GND@0") (pinfunction "GND_GND@0") (pintype "power_in"))
      (node (ref "U$6") (pin "GND") (pinfunction "GND_GND") (pintype "power_in"))
      (node (ref "U$6") (pin "GND@0") (pinfunction "GND_GND@0") (pintype "power_in"))
      (node (ref "U$7") (pin "GND") (pinfunction "GND_GND") (pintype "power_in"))
      (node (ref "U$7") (pin "GND@0") (pinfunction "GND_GND@0") (pintype "power_in"))
      (node (ref "U$8") (pin "GND") (pinfunction "GND_GND") (pintype "power_in"))
      (node (ref "U$8") (pin "GND@0") (pinfunction "GND_GND@0") (pintype "power_in"))
      (node (ref "U$9") (pin "GND") (pinfunction "GND_GND") (pintype "power_in"))
      (node (ref "U$9") (pin "GND@0") (pinfunction "GND_GND@0") (pintype "power_in"))
      (node (ref "U1") (pin "10") (pinfunction "VSS_2_10") (pintype "power_in"))
      (node (ref "U1") (pin "20") (pinfunction "VSSA/VREF-_20") (pintype "power_in"))
      (node (ref "U1") (pin "27") (pinfunction "VSS_3_27") (pintype "power_in"))
      (node (ref "U1") (pin "49") (pinfunction "VSS_4_49") (pintype "power_in"))
      (node (ref "U1") (pin "74") (pinfunction "VSS_5_74") (pintype "power_in"))
      (node (ref "U1") (pin "99") (pinfunction "VSS_99") (pintype "power_in"))
      (node (ref "U2") (pin "1") (pinfunction "GND_1") (pintype "bidirectional"))
      (node (ref "U3") (pin "5") (pinfunction "GND_5") (pintype "power_in"))
      (node (ref "U3") (pin "9") (pinfunction "GND_9") (pintype "power_in"))
      (node (ref "U4") (pin "12") (pinfunction "GND_12") (pintype "bidirectional"))
      (node (ref "U5") (pin "5") (pinfunction "GND_5") (pintype "power_in"))
      (node (ref "U5") (pin "9") (pinfunction "GND_9") (pintype "power_in"))
      (node (ref "X10") (pin "P$2") (pinfunction "1_P$2") (pintype "passive"))
      (node (ref "X11") (pin "P$2") (pinfunction "1_P$2") (pintype "passive"))
      (node (ref "X12") (pin "P$2") (pinfunction "1_P$2") (pintype "passive"))
      (node (ref "X19") (pin "P$5") (pinfunction "1_P$5") (pintype "passive"))
      (node (ref "X20") (pin "P$5") (pinfunction "1_P$5") (pintype "passive"))
      (node (ref "X21") (pin "P$4") (pinfunction "1_P$4") (pintype "passive"))
      (node (ref "X22") (pin "2") (pinfunction "2_2") (pintype "bidirectional"))
      (node (ref "X23") (pin "P$1") (pinfunction "1_P$1") (pintype "passive"))
      (node (ref "X24") (pin "P$1") (pinfunction "1_P$1") (pintype "passive"))
      (node (ref "X26") (pin "P$5") (pinfunction "1_P$5") (pintype "passive"))
      (node (ref "X27") (pin "P$5") (pinfunction "1_P$5") (pintype "passive"))
      (node (ref "X28") (pin "P$5") (pinfunction "1_P$5") (pintype "passive"))
      (node (ref "X29") (pin "P$1") (pinfunction "1_P$1") (pintype "passive"))
      (node (ref "X30") (pin "P$1") (pinfunction "1_P$1") (pintype "passive"))
      (node (ref "X31") (pin "P$1") (pinfunction "1_P$1") (pintype "passive"))
      (node (ref "X32") (pin "P$1") (pinfunction "1_P$1") (pintype "passive"))
      (node (ref "X7") (pin "P$2") (pinfunction "1_P$2") (pintype "passive"))
      (node (ref "X8") (pin "P$2") (pinfunction "1_P$2") (pintype "passive"))
      (node (ref "X9") (pin "P$2") (pinfunction "1_P$2") (pintype "passive"))
      (node (ref "Y1") (pin "2_GND") (pinfunction "2_2_GND") (pintype "bidirectional"))
      (node (ref "Y1") (pin "4_GND") (pinfunction "2_4_GND") (pintype "bidirectional"))
      (node (ref "Y2") (pin "2_GND") (pinfunction "2_2_GND") (pintype "bidirectional"))
      (node (ref "Y2") (pin "4_GND") (pinfunction "2_4_GND") (pintype "bidirectional"))
      (node (ref "Y3") (pin "2_GND") (pinfunction "2_2_GND") (pintype "bidirectional"))
      (node (ref "Y3") (pin "4_GND") (pinfunction "2_4_GND") (pintype "bidirectional"))
    )
    (net (code "16") (name "INPUT_RESERVED_1") (class "Default")
      (node (ref "C27") (pin "1") (pinfunction "1_1") (pintype "bidirectional"))
      (node (ref "R12") (pin "2") (pinfunction "2_2") (pintype "passive"))
      (node (ref "U1") (pin "45") (pinfunction "PE14_45") (pintype "bidirectional"))
    )
    (net (code "17") (name "INPUT_RESERVED_2") (class "Default")
      (node (ref "C28") (pin "1") (pinfunction "1_1") (pintype "bidirectional"))
      (node (ref "R14") (pin "2") (pinfunction "2_2") (pintype "passive"))
      (node (ref "U1") (pin "44") (pinfunction "PE13_44") (pintype "bidirectional"))
    )
    (net (code "18") (name "INPUT_X_END") (class "Default")
      (node (ref "C23") (pin "1") (pinfunction "1_1") (pintype "bidirectional"))
      (node (ref "R5") (pin "2") (pinfunction "2_2") (pintype "passive"))
      (node (ref "U1") (pin "57") (pinfunction "PD10_57") (pintype "bidirectional"))
    )
    (net (code "19") (name "INPUT_Y_END1") (class "Default")
      (node (ref "C24") (pin "1") (pinfunction "1_1") (pintype "bidirectional"))
      (node (ref "R6") (pin "2") (pinfunction "2_2") (pintype "passive"))
      (node (ref "U1") (pin "56") (pinfunction "PD9_56") (pintype "bidirectional"))
    )
    (net (code "20") (name "INPUT_Y_END2") (class "Default")
      (node (ref "C25") (pin "1") (pinfunction "1_1") (pintype "bidirectional"))
      (node (ref "R8") (pin "2") (pinfunction "2_2") (pintype "passive"))
      (node (ref "U1") (pin "55") (pinfunction "PD8_55") (pintype "bidirectional"))
    )
    (net (code "21") (name "INPUT_Z_END") (class "Default")
      (node (ref "C26") (pin "1") (pinfunction "1_1") (pintype "bidirectional"))
      (node (ref "R10") (pin "2") (pinfunction "2_2") (pintype "passive"))
      (node (ref "U1") (pin "46") (pinfunction "PE15_46") (pintype "bidirectional"))
    )
    (net (code "22") (name "MOT_A_DIR") (class "Default")
      (node (ref "U$7") (pin "DIR") (pinfunction "DIR_DIR") (pintype "input"))
      (node (ref "U1") (pin "82") (pinfunction "PD1_82") (pintype "bidirectional"))
    )
    (net (code "23") (name "MOT_A_EN") (class "Default")
      (node (ref "U$7") (pin "EN") (pinfunction "EN_EN") (pintype "input"))
      (node (ref "U1") (pin "84") (pinfunction "PD3_84") (pintype "bidirectional"))
    )
    (net (code "24") (name "MOT_A_STEP") (class "Default")
      (node (ref "U$7") (pin "STEP") (pinfunction "STEP_STEP") (pintype "input"))
      (node (ref "U1") (pin "83") (pinfunction "PD2_83") (pintype "bidirectional"))
    )
    (net (code "25") (name "MOT_B_DIR") (class "Default")
      (node (ref "U$8") (pin "DIR") (pinfunction "DIR_DIR") (pintype "input"))
      (node (ref "U1") (pin "64") (pinfunction "PC7_64") (pintype "bidirectional"))
    )
    (net (code "26") (name "MOT_B_EN") (class "Default")
      (node (ref "U$8") (pin "EN") (pinfunction "EN_EN") (pintype "input"))
      (node (ref "U1") (pin "66") (pinfunction "PC9_66") (pintype "bidirectional"))
    )
    (net (code "27") (name "MOT_B_STEP") (class "Default")
      (node (ref "U$8") (pin "STEP") (pinfunction "STEP_STEP") (pintype "input"))
      (node (ref "U1") (pin "65") (pinfunction "PC8_65") (pintype "bidirectional"))
    )
    (net (code "28") (name "MOT_C_DIR") (class "Default")
      (node (ref "U$9") (pin "DIR") (pinfunction "DIR_DIR") (pintype "input"))
      (node (ref "U1") (pin "79") (pinfunction "PC11_79") (pintype "bidirectional"))
    )
    (net (code "29") (name "MOT_C_EN") (class "Default")
      (node (ref "U$9") (pin "EN") (pinfunction "EN_EN") (pintype "input"))
      (node (ref "U1") (pin "81") (pinfunction "PD0_81") (pintype "bidirectional"))
    )
    (net (code "30") (name "MOT_C_STEP") (class "Default")
      (node (ref "U$9") (pin "STEP") (pinfunction "STEP_STEP") (pintype "input"))
      (node (ref "U1") (pin "80") (pinfunction "PC12_80") (pintype "bidirectional"))
    )
    (net (code "31") (name "MOT_E_DIR") (class "Default")
      (node (ref "U$6") (pin "DIR") (pinfunction "DIR_DIR") (pintype "input"))
      (node (ref "U1") (pin "85") (pinfunction "PD4_85") (pintype "bidirectional"))
    )
    (net (code "32") (name "MOT_E_EN") (class "Default")
      (node (ref "U$6") (pin "EN") (pinfunction "EN_EN") (pintype "input"))
      (node (ref "U1") (pin "87") (pinfunction "PD6_87") (pintype "bidirectional"))
    )
    (net (code "33") (name "MOT_E_STEP") (class "Default")
      (node (ref "U$6") (pin "STEP") (pinfunction "STEP_STEP") (pintype "input"))
      (node (ref "U1") (pin "86") (pinfunction "PD5_86") (pintype "bidirectional"))
    )
    (net (code "34") (name "MOT_MS1") (class "Default")
      (node (ref "U$2") (pin "MS1") (pinfunction "MS1_MS1") (pintype "input"))
      (node (ref "U$3") (pin "MS1") (pinfunction "MS1_MS1") (pintype "input"))
      (node (ref "U$4") (pin "MS1") (pinfunction "MS1_MS1") (pintype "input"))
      (node (ref "U$5") (pin "MS1") (pinfunction "MS1_MS1") (pintype "input"))
      (node (ref "U$6") (pin "MS1") (pinfunction "MS1_MS1") (pintype "input"))
      (node (ref "U$7") (pin "MS1") (pinfunction "MS1_MS1") (pintype "input"))
      (node (ref "U$8") (pin "MS1") (pinfunction "MS1_MS1") (pintype "input"))
      (node (ref "U$9") (pin "MS1") (pinfunction "MS1_MS1") (pintype "input"))
      (node (ref "U1") (pin "41") (pinfunction "PE10_41") (pintype "bidirectional"))
    )
    (net (code "35") (name "MOT_MS2") (class "Default")
      (node (ref "U$2") (pin "MS2") (pinfunction "MS2_MS2") (pintype "input"))
      (node (ref "U$3") (pin "MS2") (pinfunction "MS2_MS2") (pintype "input"))
      (node (ref "U$4") (pin "MS2") (pinfunction "MS2_MS2") (pintype "input"))
      (node (ref "U$5") (pin "MS2") (pinfunction "MS2_MS2") (pintype "input"))
      (node (ref "U$6") (pin "MS2") (pinfunction "MS2_MS2") (pintype "input"))
      (node (ref "U$7") (pin "MS2") (pinfunction "MS2_MS2") (pintype "input"))
      (node (ref "U$8") (pin "MS2") (pinfunction "MS2_MS2") (pintype "input"))
      (node (ref "U$9") (pin "MS2") (pinfunction "MS2_MS2") (pintype "input"))
      (node (ref "U1") (pin "42") (pinfunction "PE11_42") (pintype "bidirectional"))
    )
    (net (code "36") (name "MOT_MS3") (class "Default")
      (node (ref "U$2") (pin "MS3") (pinfunction "MS3_MS3") (pintype "input"))
      (node (ref "U$3") (pin "MS3") (pinfunction "MS3_MS3") (pintype "input"))
      (node (ref "U$4") (pin "MS3") (pinfunction "MS3_MS3") (pintype "input"))
      (node (ref "U$5") (pin "MS3") (pinfunction "MS3_MS3") (pintype "input"))
      (node (ref "U$6") (pin "MS3") (pinfunction "MS3_MS3") (pintype "input"))
      (node (ref "U$7") (pin "MS3") (pinfunction "MS3_MS3") (pintype "input"))
      (node (ref "U$8") (pin "MS3") (pinfunction "MS3_MS3") (pintype "input"))
      (node (ref "U$9") (pin "MS3") (pinfunction "MS3_MS3") (pintype "input"))
      (node (ref "U1") (pin "43") (pinfunction "PE12_43") (pintype "bidirectional"))
    )
    (net (code "37") (name "MOT_X_DIR") (class "Default")
      (node (ref "U$2") (pin "DIR") (pinfunction "DIR_DIR") (pintype "input"))
      (node (ref "U1") (pin "3") (pinfunction "PE4_3") (pintype "bidirectional"))
    )
    (net (code "38") (name "MOT_X_EN") (class "Default")
      (node (ref "U$2") (pin "EN") (pinfunction "EN_EN") (pintype "input"))
      (node (ref "U1") (pin "5") (pinfunction "PE6_5") (pintype "bidirectional"))
    )
    (net (code "39") (name "MOT_X_STEP") (class "Default")
      (node (ref "U$2") (pin "STEP") (pinfunction "STEP_STEP") (pintype "input"))
      (node (ref "U1") (pin "4") (pinfunction "PE5_4") (pintype "bidirectional"))
    )
    (net (code "40") (name "MOT_Y0_DIR") (class "Default")
      (node (ref "U$3") (pin "DIR") (pinfunction "DIR_DIR") (pintype "input"))
      (node (ref "U1") (pin "98") (pinfunction "PE1_98") (pintype "bidirectional"))
    )
    (net (code "41") (name "MOT_Y0_EN") (class "Default")
      (node (ref "U$3") (pin "EN") (pinfunction "EN_EN") (pintype "input"))
      (node (ref "U1") (pin "2") (pinfunction "PE3_2") (pintype "bidirectional"))
    )
    (net (code "42") (name "MOT_Y0_STEP") (class "Default")
      (node (ref "U$3") (pin "STEP") (pinfunction "STEP_STEP") (pintype "input"))
      (node (ref "U1") (pin "1") (pinfunction "PE2_1") (pintype "bidirectional"))
    )
    (net (code "43") (name "MOT_Y1_DIR") (class "Default")
      (node (ref "U$4") (pin "DIR") (pinfunction "DIR_DIR") (pintype "input"))
      (node (ref "U1") (pin "95") (pinfunction "PB8_95") (pintype "bidirectional"))
    )
    (net (code "44") (name "MOT_Y1_EN") (class "Default")
      (node (ref "U$4") (pin "EN") (pinfunction "EN_EN") (pintype "input"))
      (node (ref "U1") (pin "97") (pinfunction "PE0_97") (pintype "bidirectional"))
    )
    (net (code "45") (name "MOT_Y1_STEP") (class "Default")
      (node (ref "U$4") (pin "STEP") (pinfunction "STEP_STEP") (pintype "input"))
      (node (ref "U1") (pin "96") (pinfunction "PB9_96") (pintype "bidirectional"))
    )
    (net (code "46") (name "MOT_Z_DIR") (class "Default")
      (node (ref "U$5") (pin "DIR") (pinfunction "DIR_DIR") (pintype "input"))
      (node (ref "U1") (pin "88") (pinfunction "PD7_88") (pintype "bidirectional"))
    )
    (net (code "47") (name "MOT_Z_EN") (class "Default")
      (node (ref "U$5") (pin "EN") (pinfunction "EN_EN") (pintype "input"))
      (node (ref "U1") (pin "91") (pinfunction "PB5_91") (pintype "bidirectional"))
    )
    (net (code "48") (name "MOT_Z_STEP") (class "Default")
      (node (ref "U$5") (pin "STEP") (pinfunction "STEP_STEP") (pintype "input"))
      (node (ref "U1") (pin "90") (pinfunction "PB4_90") (pintype "bidirectional"))
    )
    (net (code "49") (name "NRST") (class "Default")
      (node (ref "C29") (pin "1") (pinfunction "1_1") (pintype "bidirectional"))
      (node (ref "R29") (pin "2") (pinfunction "2_2") (pintype "passive"))
      (node (ref "S1") (pin "1A") (pinfunction "1_1A") (pintype "bidirectional"))
      (node (ref "S1") (pin "1B") (pinfunction "2_1B") (pintype "bidirectional"))
      (node (ref "U1") (pin "14") (pinfunction "NRST_14") (pintype "bidirectional"))
      (node (ref "X21") (pin "P$3") (pinfunction "1_P$3") (pintype "passive"))
    )
    (net (code "50") (name "Net-(C1-1)") (class "Default")
      (node (ref "C1") (pin "P$1") (pinfunction "1_P$1") (pintype "bidirectional"))
      (node (ref "C43") (pin "1") (pinfunction "1_1") (pintype "bidirectional"))
      (node (ref "U1") (pin "48") (pinfunction "VCAP_1_48") (pintype "power_in"))
      (node (ref "U1") (pin "73") (pinfunction "VCAP_2_73") (pintype "power_in"))
    )
    (net (code "51") (name "Net-(C36-2)") (class "Default")
      (node (ref "C36") (pin "P$2") (pinfunction "2_P$2") (pintype "bidirectional"))
      (node (ref "U4") (pin "14") (pinfunction "VDD18_14") (pintype "bidirectional"))
    )
    (net (code "52") (name "Net-(C39-2)") (class "Default")
      (node (ref "C39") (pin "P$2") (pinfunction "2_P$2") (pintype "bidirectional"))
      (node (ref "U4") (pin "13") (pinfunction "VDD3_13") (pintype "bidirectional"))
    )
    (net (code "53") (name "Net-(D1-Pad2)") (class "Default")
      (node (ref "D1") (pin "2") (pinfunction "2_2") (pintype "bidirectional"))
      (node (ref "R18") (pin "2") (pinfunction "2_2") (pintype "passive"))
    )
    (net (code "54") (name "Net-(D2-ANODE)") (class "Default")
      (node (ref "D2") (pin "A") (pinfunction "ANODE_A") (pintype "bidirectional"))
      (node (ref "R20") (pin "1") (pinfunction "1_1") (pintype "passive"))
      (node (ref "U$22") (pin "D") (pinfunction "D_D") (pintype "bidirectional"))
      (node (ref "X14") (pin "P$1") (pinfunction "1_P$1") (pintype "passive"))
    )
    (net (code "55") (name "Net-(D3-Pad2)") (class "Default")
      (node (ref "D3") (pin "2") (pinfunction "2_2") (pintype "bidirectional"))
      (node (ref "R20") (pin "2") (pinfunction "2_2") (pintype "passive"))
    )
    (net (code "56") (name "Net-(D4-Pad2)") (class "Default")
      (node (ref "D4") (pin "2") (pinfunction "2_2") (pintype "bidirectional"))
      (node (ref "R46") (pin "2") (pinfunction "2_2") (pintype "passive"))
    )
    (net (code "57") (name "Net-(D5-ANODE)") (class "Default")
      (node (ref "D5") (pin "A") (pinfunction "ANODE_A") (pintype "bidirectional"))
      (node (ref "R22") (pin "1") (pinfunction "1_1") (pintype "passive"))
      (node (ref "U$23") (pin "D") (pinfunction "D_D") (pintype "bidirectional"))
      (node (ref "X15") (pin "P$1") (pinfunction "1_P$1") (pintype "passive"))
    )
    (net (code "58") (name "Net-(D6-Pad2)") (class "Default")
      (node (ref "D6") (pin "2") (pinfunction "2_2") (pintype "bidirectional"))
      (node (ref "R22") (pin "2") (pinfunction "2_2") (pintype "passive"))
    )
    (net (code "59") (name "Net-(D7-ANODE)") (class "Default")
      (node (ref "D7") (pin "A") (pinfunction "ANODE_A") (pintype "bidirectional"))
      (node (ref "R24") (pin "1") (pinfunction "1_1") (pintype "passive"))
      (node (ref "U$24") (pin "D") (pinfunction "D_D") (pintype "bidirectional"))
      (node (ref "X16") (pin "P$1") (pinfunction "1_P$1") (pintype "passive"))
    )
    (net (code "60") (name "Net-(D8-Pad2)") (class "Default")
      (node (ref "D8") (pin "2") (pinfunction "2_2") (pintype "bidirectional"))
      (node (ref "R24") (pin "2") (pinfunction "2_2") (pintype "passive"))
    )
    (net (code "61") (name "Net-(D9-ANODE)") (class "Default")
      (node (ref "D9") (pin "A") (pinfunction "ANODE_A") (pintype "bidirectional"))
      (node (ref "R26") (pin "1") (pinfunction "1_1") (pintype "passive"))
      (node (ref "U$25") (pin "D") (pinfunction "D_D") (pintype "bidirectional"))
      (node (ref "X17") (pin "P$1") (pinfunction "1_P$1") (pintype "passive"))
    )
    (net (code "62") (name "Net-(D10-Pad1)") (class "Default")
      (node (ref "D10") (pin "1") (pinfunction "1_1") (pintype "bidirectional"))
      (node (ref "F1") (pin "2") (pinfunction "2_2") (pintype "passive"))
    )
    (net (code "63") (name "Net-(D11-Pad2)") (class "Default")
      (node (ref "D11") (pin "2") (pinfunction "2_2") (pintype "bidirectional"))
      (node (ref "R26") (pin "2") (pinfunction "2_2") (pintype "passive"))
    )
    (net (code "64") (name "Net-(D12-Pad2)") (class "Default")
      (node (ref "D12") (pin "2") (pinfunction "2_2") (pintype "bidirectional"))
      (node (ref "R47") (pin "2") (pinfunction "2_2") (pintype "passive"))
    )
    (net (code "65") (name "Net-(D13-ANODE)") (class "Default")
      (node (ref "D13") (pin "A") (pinfunction "ANODE_A") (pintype "bidirectional"))
      (node (ref "R18") (pin "1") (pinfunction "1_1") (pintype "passive"))
      (node (ref "U$21") (pin "D") (pinfunction "D_D") (pintype "bidirectional"))
      (node (ref "X13") (pin "P$1") (pinfunction "1_P$1") (pintype "passive"))
    )
    (net (code "66") (name "Net-(D14-ANODE)") (class "Default")
      (node (ref "D14") (pin "A") (pinfunction "ANODE_A") (pintype "bidirectional"))
      (node (ref "R28") (pin "1") (pinfunction "1_1") (pintype "passive"))
      (node (ref "U$26") (pin "D") (pinfunction "D_D") (pintype "bidirectional"))
      (node (ref "X18") (pin "P$1") (pinfunction "1_P$1") (pintype "passive"))
    )
    (net (code "67") (name "Net-(D15-Pad2)") (class "Default")
      (node (ref "D15") (pin "2") (pinfunction "2_2") (pintype "bidirectional"))
      (node (ref "R28") (pin "2") (pinfunction "2_2") (pintype "passive"))
    )
    (net (code "68") (name "Net-(D17-Pad2)") (class "Default")
      (node (ref "D17") (pin "2") (pinfunction "2_2") (pintype "bidirectional"))
      (node (ref "R48") (pin "2") (pinfunction "2_2") (pintype "passive"))
    )
    (net (code "69") (name "Net-(D18-Pad2)") (class "Default")
      (node (ref "D18") (pin "2") (pinfunction "2_2") (pintype "bidirectional"))
      (node (ref "R49") (pin "2") (pinfunction "2_2") (pintype "passive"))
    )
    (net (code "70") (name "Net-(D19-Pad2)") (class "Default")
      (node (ref "D19") (pin "2") (pinfunction "2_2") (pintype "bidirectional"))
      (node (ref "R50") (pin "2") (pinfunction "2_2") (pintype "passive"))
    )
    (net (code "71") (name "Net-(D20-Pad2)") (class "Default")
      (node (ref "D20") (pin "2") (pinfunction "2_2") (pintype "bidirectional"))
      (node (ref "R51") (pin "2") (pinfunction "2_2") (pintype "passive"))
    )
    (net (code "72") (name "Net-(J1-+5V)") (class "Default")
      (node (ref "F1") (pin "1") (pinfunction "1_1") (pintype "passive"))
      (node (ref "J1") (pin "1") (pinfunction "+5V_1") (pintype "bidirectional"))
    )
    (net (code "73") (name "Net-(L1-1)") (class "Default")
      (node (ref "C50") (pin "1") (pinfunction "1_1") (pintype "bidirectional"))
      (node (ref "L1") (pin "P$1") (pinfunction "1_P$1") (pintype "passive"))
      (node (ref "U3") (pin "6") (pinfunction "SW_6") (pintype "output"))
    )
    (net (code "74") (name "Net-(L2-1)") (class "Default")
      (node (ref "C57") (pin "1") (pinfunction "1_1") (pintype "bidirectional"))
      (node (ref "L2") (pin "P$1") (pinfunction "1_P$1") (pintype "passive"))
      (node (ref "U5") (pin "6") (pinfunction "SW_6") (pintype "output"))
    )
    (net (code "75") (name "Net-(R17-Pad2)") (class "Default")
      (node (ref "R17") (pin "2") (pinfunction "2_2") (pintype "passive"))
      (node (ref "R40") (pin "1") (pinfunction "1_1") (pintype "passive"))
      (node (ref "U$21") (pin "G") (pinfunction "G_G") (pintype "bidirectional"))
    )
    (net (code "76") (name "Net-(R19-Pad2)") (class "Default")
      (node (ref "R19") (pin "2") (pinfunction "2_2") (pintype "passive"))
      (node (ref "R41") (pin "1") (pinfunction "1_1") (pintype "passive"))
      (node (ref "U$22") (pin "G") (pinfunction "G_G") (pintype "bidirectional"))
    )
    (net (code "77") (name "Net-(R21-Pad2)") (class "Default")
      (node (ref "R21") (pin "2") (pinfunction "2_2") (pintype "passive"))
      (node (ref "R42") (pin "1") (pinfunction "1_1") (pintype "passive"))
      (node (ref "U$23") (pin "G") (pinfunction "G_G") (pintype "bidirectional"))
    )
    (net (code "78") (name "Net-(R23-Pad2)") (class "Default")
      (node (ref "R23") (pin "2") (pinfunction "2_2") (pintype "passive"))
      (node (ref "R43") (pin "1") (pinfunction "1_1") (pintype "passive"))
      (node (ref "U$24") (pin "G") (pinfunction "G_G") (pintype "bidirectional"))
    )
    (net (code "79") (name "Net-(R25-Pad2)") (class "Default")
      (node (ref "R25") (pin "2") (pinfunction "2_2") (pintype "passive"))
      (node (ref "R44") (pin "1") (pinfunction "1_1") (pintype "passive"))
      (node (ref "U$25") (pin "G") (pinfunction "G_G") (pintype "bidirectional"))
    )
    (net (code "80") (name "Net-(R27-Pad2)") (class "Default")
      (node (ref "R27") (pin "2") (pinfunction "2_2") (pintype "passive"))
      (node (ref "R45") (pin "1") (pinfunction "1_1") (pintype "passive"))
      (node (ref "U$26") (pin "G") (pinfunction "G_G") (pintype "bidirectional"))
    )
    (net (code "81") (name "Net-(R38-Pad1)") (class "Default")
      (node (ref "R38") (pin "1") (pinfunction "1_1") (pintype "passive"))
      (node (ref "R39") (pin "1") (pinfunction "1_1") (pintype "passive"))
    )
    (net (code "82") (name "Net-(U$2-SLEEP)") (class "Default")
      (node (ref "U$2") (pin "RST") (pinfunction "RST_RST") (pintype "input"))
      (node (ref "U$2") (pin "SLP") (pinfunction "SLEEP_SLP") (pintype "input"))
    )
    (net (code "83") (name "Net-(U$3-SLEEP)") (class "Default")
      (node (ref "U$3") (pin "RST") (pinfunction "RST_RST") (pintype "input"))
      (node (ref "U$3") (pin "SLP") (pinfunction "SLEEP_SLP") (pintype "input"))
    )
    (net (code "84") (name "Net-(U$4-SLEEP)") (class "Default")
      (node (ref "U$4") (pin "RST") (pinfunction "RST_RST") (pintype "input"))
      (node (ref "U$4") (pin "SLP") (pinfunction "SLEEP_SLP") (pintype "input"))
    )
    (net (code "85") (name "Net-(U$5-SLEEP)") (class "Default")
      (node (ref "U$5") (pin "RST") (pinfunction "RST_RST") (pintype "input"))
      (node (ref "U$5") (pin "SLP") (pinfunction "SLEEP_SLP") (pintype "input"))
    )
    (net (code "86") (name "Net-(U$6-SLEEP)") (class "Default")
      (node (ref "U$6") (pin "RST") (pinfunction "RST_RST") (pintype "input"))
      (node (ref "U$6") (pin "SLP") (pinfunction "SLEEP_SLP") (pintype "input"))
    )
    (net (code "87") (name "Net-(U$7-SLEEP)") (class "Default")
      (node (ref "U$7") (pin "RST") (pinfunction "RST_RST") (pintype "input"))
      (node (ref "U$7") (pin "SLP") (pinfunction "SLEEP_SLP") (pintype "input"))
    )
    (net (code "88") (name "Net-(U$8-SLEEP)") (class "Default")
      (node (ref "U$8") (pin "RST") (pinfunction "RST_RST") (pintype "input"))
      (node (ref "U$8") (pin "SLP") (pinfunction "SLEEP_SLP") (pintype "input"))
    )
    (net (code "89") (name "Net-(U$9-SLEEP)") (class "Default")
      (node (ref "U$9") (pin "RST") (pinfunction "RST_RST") (pintype "input"))
      (node (ref "U$9") (pin "SLP") (pinfunction "SLEEP_SLP") (pintype "input"))
    )
    (net (code "90") (name "Net-(U1A-PB1)") (class "Default")
      (node (ref "D4") (pin "1") (pinfunction "1_1") (pintype "bidirectional"))
      (node (ref "U1") (pin "36") (pinfunction "PB1_36") (pintype "bidirectional"))
    )
    (net (code "91") (name "Net-(U1A-PB2)") (class "Default")
      (node (ref "D12") (pin "1") (pinfunction "1_1") (pintype "bidirectional"))
      (node (ref "U1") (pin "37") (pinfunction "PB2_37") (pintype "bidirectional"))
    )
    (net (code "92") (name "Net-(U1A-PB13)") (class "Default")
      (node (ref "D17") (pin "1") (pinfunction "1_1") (pintype "bidirectional"))
      (node (ref "U1") (pin "52") (pinfunction "PB13_52") (pintype "bidirectional"))
    )
    (net (code "93") (name "Net-(U1A-PB14)") (class "Default")
      (node (ref "D18") (pin "1") (pinfunction "1_1") (pintype "bidirectional"))
      (node (ref "U1") (pin "53") (pinfunction "PB14_53") (pintype "bidirectional"))
    )
    (net (code "94") (name "Net-(U1B-BOOT0)") (class "Default")
      (node (ref "R30") (pin "1") (pinfunction "1_1") (pintype "passive"))
      (node (ref "U1") (pin "94") (pinfunction "BOOT0_94") (pintype "input"))
    )
    (net (code "95") (name "Net-(U1B-PH0-OSC_IN)") (class "Default")
      (node (ref "C30") (pin "1") (pinfunction "1_1") (pintype "bidirectional"))
      (node (ref "U1") (pin "12") (pinfunction "PH0-OSC_IN_12") (pintype "bidirectional"))
      (node (ref "Y1") (pin "3") (pinfunction "3_3") (pintype "bidirectional"))
    )
    (net (code "96") (name "Net-(U1B-PH1)") (class "Default")
      (node (ref "C31") (pin "1") (pinfunction "1_1") (pintype "bidirectional"))
      (node (ref "U1") (pin "13") (pinfunction "PH1_13") (pintype "bidirectional"))
      (node (ref "Y1") (pin "1") (pinfunction "1_1") (pintype "bidirectional"))
    )
    (net (code "97") (name "Net-(U2-DTR#)") (class "Default")
      (node (ref "R3") (pin "1") (pinfunction "1_1") (pintype "passive"))
      (node (ref "U2") (pin "13") (pinfunction "DTR#_13") (pintype "bidirectional"))
    )
    (net (code "98") (name "Net-(U2-RXD)") (class "Default")
      (node (ref "R2") (pin "1") (pinfunction "1_1") (pintype "passive"))
      (node (ref "U2") (pin "3") (pinfunction "RXD_3") (pintype "bidirectional"))
    )
    (net (code "99") (name "Net-(U2-TXD)") (class "Default")
      (node (ref "R1") (pin "1") (pinfunction "1_1") (pintype "passive"))
      (node (ref "U2") (pin "2") (pinfunction "TXD_2") (pintype "bidirectional"))
    )
    (net (code "100") (name "Net-(U2-V3)") (class "Default")
      (node (ref "C16") (pin "2") (pinfunction "2_2") (pintype "bidirectional"))
      (node (ref "U2") (pin "4") (pinfunction "V3_4") (pintype "bidirectional"))
    )
    (net (code "101") (name "Net-(U2-XI)") (class "Default")
      (node (ref "C18") (pin "2") (pinfunction "2_2") (pintype "bidirectional"))
      (node (ref "U2") (pin "7") (pinfunction "XI_7") (pintype "bidirectional"))
      (node (ref "Y2") (pin "1") (pinfunction "1_1") (pintype "bidirectional"))
    )
    (net (code "102") (name "Net-(U2-XO)") (class "Default")
      (node (ref "C19") (pin "2") (pinfunction "2_2") (pintype "bidirectional"))
      (node (ref "U2") (pin "8") (pinfunction "XO_8") (pintype "bidirectional"))
      (node (ref "Y2") (pin "3") (pinfunction "3_3") (pintype "bidirectional"))
    )
    (net (code "103") (name "Net-(U3-EN)") (class "Default")
      (node (ref "R33") (pin "2") (pinfunction "2_2") (pintype "passive"))
      (node (ref "U3") (pin "1") (pinfunction "EN_1") (pintype "input"))
    )
    (net (code "104") (name "Net-(U3-SS)") (class "Default")
      (node (ref "C52") (pin "1") (pinfunction "1_1") (pintype "bidirectional"))
      (node (ref "U3") (pin "4") (pinfunction "SS_4") (pintype "output"))
    )
    (net (code "105") (name "Net-(U3-VBST)") (class "Default")
      (node (ref "C50") (pin "2") (pinfunction "2_2") (pintype "bidirectional"))
      (node (ref "U3") (pin "7") (pinfunction "VBST_7") (pintype "input"))
    )
    (net (code "106") (name "Net-(U3-VFB)") (class "Default")
      (node (ref "C51") (pin "2") (pinfunction "2_2") (pintype "bidirectional"))
      (node (ref "R34") (pin "1") (pinfunction "1_1") (pintype "passive"))
      (node (ref "R35") (pin "2") (pinfunction "2_2") (pintype "passive"))
      (node (ref "U3") (pin "2") (pinfunction "VFB_2") (pintype "input"))
    )
    (net (code "107") (name "Net-(U3-VREG5)") (class "Default")
      (node (ref "C53") (pin "1") (pinfunction "1_1") (pintype "bidirectional"))
      (node (ref "U3") (pin "3") (pinfunction "VREG5_3") (pintype "bidirectional"))
    )
    (net (code "108") (name "Net-(U4-XIN)") (class "Default")
      (node (ref "C41") (pin "1") (pinfunction "1_1") (pintype "bidirectional"))
      (node (ref "U4") (pin "16") (pinfunction "XIN_16") (pintype "bidirectional"))
      (node (ref "Y3") (pin "3") (pinfunction "3_3") (pintype "bidirectional"))
    )
    (net (code "109") (name "Net-(U4-XOUT)") (class "Default")
      (node (ref "C4") (pin "1") (pinfunction "1_1") (pintype "bidirectional"))
      (node (ref "U4") (pin "15") (pinfunction "XOUT_15") (pintype "bidirectional"))
      (node (ref "Y3") (pin "1") (pinfunction "1_1") (pintype "bidirectional"))
    )
    (net (code "110") (name "Net-(U5-EN)") (class "Default")
      (node (ref "R36") (pin "2") (pinfunction "2_2") (pintype "passive"))
      (node (ref "U5") (pin "1") (pinfunction "EN_1") (pintype "input"))
    )
    (net (code "111") (name "Net-(U5-SS)") (class "Default")
      (node (ref "C59") (pin "1") (pinfunction "1_1") (pintype "bidirectional"))
      (node (ref "U5") (pin "4") (pinfunction "SS_4") (pintype "output"))
    )
    (net (code "112") (name "Net-(U5-VBST)") (class "Default")
      (node (ref "C57") (pin "2") (pinfunction "2_2") (pintype "bidirectional"))
      (node (ref "U5") (pin "7") (pinfunction "VBST_7") (pintype "input"))
    )
    (net (code "113") (name "Net-(U5-VFB)") (class "Default")
      (node (ref "C58") (pin "2") (pinfunction "2_2") (pintype "bidirectional"))
      (node (ref "R37") (pin "1") (pinfunction "1_1") (pintype "passive"))
      (node (ref "R38") (pin "2") (pinfunction "2_2") (pintype "passive"))
      (node (ref "U5") (pin "2") (pinfunction "VFB_2") (pintype "input"))
    )
    (net (code "114") (name "Net-(U5-VREG5)") (class "Default")
      (node (ref "C60") (pin "1") (pinfunction "1_1") (pintype "bidirectional"))
      (node (ref "U5") (pin "3") (pinfunction "VREG5_3") (pintype "bidirectional"))
    )
    (net (code "115") (name "Net-(X1A-1)") (class "Default")
      (node (ref "U$2") (pin "2B") (pinfunction "2B_2B") (pintype "output"))
      (node (ref "X1") (pin "P$1") (pinfunction "1_P$1") (pintype "passive"))
    )
    (net (code "116") (name "Net-(X1B-1)") (class "Default")
      (node (ref "U$2") (pin "2A") (pinfunction "2A_2A") (pintype "output"))
      (node (ref "X1") (pin "P$2") (pinfunction "1_P$2") (pintype "passive"))
    )
    (net (code "117") (name "Net-(X1C-1)") (class "Default")
      (node (ref "U$2") (pin "1A") (pinfunction "1A_1A") (pintype "output"))
      (node (ref "X1") (pin "P$3") (pinfunction "1_P$3") (pintype "passive"))
    )
    (net (code "118") (name "Net-(X1D-1)") (class "Default")
      (node (ref "U$2") (pin "1B") (pinfunction "1B_1B") (pintype "output"))
      (node (ref "X1") (pin "P$4") (pinfunction "1_P$4") (pintype "passive"))
    )
    (net (code "119") (name "Net-(X2A-1)") (class "Default")
      (node (ref "U$3") (pin "2B") (pinfunction "2B_2B") (pintype "output"))
      (node (ref "X2") (pin "P$1") (pinfunction "1_P$1") (pintype "passive"))
    )
    (net (code "120") (name "Net-(X2B-1)") (class "Default")
      (node (ref "U$3") (pin "2A") (pinfunction "2A_2A") (pintype "output"))
      (node (ref "X2") (pin "P$2") (pinfunction "1_P$2") (pintype "passive"))
    )
    (net (code "121") (name "Net-(X2C-1)") (class "Default")
      (node (ref "U$3") (pin "1A") (pinfunction "1A_1A") (pintype "output"))
      (node (ref "X2") (pin "P$3") (pinfunction "1_P$3") (pintype "passive"))
    )
    (net (code "122") (name "Net-(X2D-1)") (class "Default")
      (node (ref "U$3") (pin "1B") (pinfunction "1B_1B") (pintype "output"))
      (node (ref "X2") (pin "P$4") (pinfunction "1_P$4") (pintype "passive"))
    )
    (net (code "123") (name "Net-(X3A-1)") (class "Default")
      (node (ref "U$4") (pin "2B") (pinfunction "2B_2B") (pintype "output"))
      (node (ref "X3") (pin "P$1") (pinfunction "1_P$1") (pintype "passive"))
    )
    (net (code "124") (name "Net-(X3B-1)") (class "Default")
      (node (ref "U$4") (pin "2A") (pinfunction "2A_2A") (pintype "output"))
      (node (ref "X3") (pin "P$2") (pinfunction "1_P$2") (pintype "passive"))
    )
    (net (code "125") (name "Net-(X3C-1)") (class "Default")
      (node (ref "U$4") (pin "1A") (pinfunction "1A_1A") (pintype "output"))
      (node (ref "X3") (pin "P$3") (pinfunction "1_P$3") (pintype "passive"))
    )
    (net (code "126") (name "Net-(X3D-1)") (class "Default")
      (node (ref "U$4") (pin "1B") (pinfunction "1B_1B") (pintype "output"))
      (node (ref "X3") (pin "P$4") (pinfunction "1_P$4") (pintype "passive"))
    )
    (net (code "127") (name "Net-(X4A-1)") (class "Default")
      (node (ref "U$5") (pin "2B") (pinfunction "2B_2B") (pintype "output"))
      (node (ref "X4") (pin "P$1") (pinfunction "1_P$1") (pintype "passive"))
    )
    (net (code "128") (name "Net-(X4B-1)") (class "Default")
      (node (ref "U$5") (pin "2A") (pinfunction "2A_2A") (pintype "output"))
      (node (ref "X4") (pin "P$2") (pinfunction "1_P$2") (pintype "passive"))
    )
    (net (code "129") (name "Net-(X4C-1)") (class "Default")
      (node (ref "U$5") (pin "1A") (pinfunction "1A_1A") (pintype "output"))
      (node (ref "X4") (pin "P$3") (pinfunction "1_P$3") (pintype "passive"))
    )
    (net (code "130") (name "Net-(X4D-1)") (class "Default")
      (node (ref "U$5") (pin "1B") (pinfunction "1B_1B") (pintype "output"))
      (node (ref "X4") (pin "P$4") (pinfunction "1_P$4") (pintype "passive"))
    )
    (net (code "131") (name "Net-(X5A-1)") (class "Default")
      (node (ref "U$6") (pin "2B") (pinfunction "2B_2B") (pintype "output"))
      (node (ref "X5") (pin "P$1") (pinfunction "1_P$1") (pintype "passive"))
    )
    (net (code "132") (name "Net-(X5B-1)") (class "Default")
      (node (ref "U$6") (pin "2A") (pinfunction "2A_2A") (pintype "output"))
      (node (ref "X5") (pin "P$2") (pinfunction "1_P$2") (pintype "passive"))
    )
    (net (code "133") (name "Net-(X5C-1)") (class "Default")
      (node (ref "U$6") (pin "1A") (pinfunction "1A_1A") (pintype "output"))
      (node (ref "X5") (pin "P$3") (pinfunction "1_P$3") (pintype "passive"))
    )
    (net (code "134") (name "Net-(X5D-1)") (class "Default")
      (node (ref "U$6") (pin "1B") (pinfunction "1B_1B") (pintype "output"))
      (node (ref "X5") (pin "P$4") (pinfunction "1_P$4") (pintype "passive"))
    )
    (net (code "135") (name "Net-(X6A-1)") (class "Default")
      (node (ref "U$7") (pin "2B") (pinfunction "2B_2B") (pintype "output"))
      (node (ref "X6") (pin "P$1") (pinfunction "1_P$1") (pintype "passive"))
    )
    (net (code "136") (name "Net-(X6B-1)") (class "Default")
      (node (ref "U$7") (pin "2A") (pinfunction "2A_2A") (pintype "output"))
      (node (ref "X6") (pin "P$2") (pinfunction "1_P$2") (pintype "passive"))
    )
    (net (code "137") (name "Net-(X6C-1)") (class "Default")
      (node (ref "U$7") (pin "1A") (pinfunction "1A_1A") (pintype "output"))
      (node (ref "X6") (pin "P$3") (pinfunction "1_P$3") (pintype "passive"))
    )
    (net (code "138") (name "Net-(X6D-1)") (class "Default")
      (node (ref "U$7") (pin "1B") (pinfunction "1B_1B") (pintype "output"))
      (node (ref "X6") (pin "P$4") (pinfunction "1_P$4") (pintype "passive"))
    )
    (net (code "139") (name "Net-(X7A-1)") (class "Default")
      (node (ref "R4") (pin "2") (pinfunction "2_2") (pintype "passive"))
      (node (ref "R5") (pin "1") (pinfunction "1_1") (pintype "passive"))
      (node (ref "X7") (pin "P$1") (pinfunction "1_P$1") (pintype "passive"))
    )
    (net (code "140") (name "Net-(X8A-1)") (class "Default")
      (node (ref "R6") (pin "1") (pinfunction "1_1") (pintype "passive"))
      (node (ref "R7") (pin "2") (pinfunction "2_2") (pintype "passive"))
      (node (ref "X8") (pin "P$1") (pinfunction "1_P$1") (pintype "passive"))
    )
    (net (code "141") (name "Net-(X9A-1)") (class "Default")
      (node (ref "R8") (pin "1") (pinfunction "1_1") (pintype "passive"))
      (node (ref "R9") (pin "2") (pinfunction "2_2") (pintype "passive"))
      (node (ref "X9") (pin "P$1") (pinfunction "1_P$1") (pintype "passive"))
    )
    (net (code "142") (name "Net-(X10A-1)") (class "Default")
      (node (ref "R10") (pin "1") (pinfunction "1_1") (pintype "passive"))
      (node (ref "R11") (pin "2") (pinfunction "2_2") (pintype "passive"))
      (node (ref "X10") (pin "P$1") (pinfunction "1_P$1") (pintype "passive"))
    )
    (net (code "143") (name "Net-(X11A-1)") (class "Default")
      (node (ref "R12") (pin "1") (pinfunction "1_1") (pintype "passive"))
      (node (ref "R13") (pin "2") (pinfunction "2_2") (pintype "passive"))
      (node (ref "X11") (pin "P$1") (pinfunction "1_P$1") (pintype "passive"))
    )
    (net (code "144") (name "Net-(X12A-1)") (class "Default")
      (node (ref "R14") (pin "1") (pinfunction "1_1") (pintype "passive"))
      (node (ref "R15") (pin "2") (pinfunction "2_2") (pintype "passive"))
      (node (ref "X12") (pin "P$1") (pinfunction "1_P$1") (pintype "passive"))
    )
    (net (code "145") (name "Net-(X25A-1)") (class "Default")
      (node (ref "U$8") (pin "2B") (pinfunction "2B_2B") (pintype "output"))
      (node (ref "X25") (pin "P$1") (pinfunction "1_P$1") (pintype "passive"))
    )
    (net (code "146") (name "Net-(X25B-1)") (class "Default")
      (node (ref "U$8") (pin "2A") (pinfunction "2A_2A") (pintype "output"))
      (node (ref "X25") (pin "P$2") (pinfunction "1_P$2") (pintype "passive"))
    )
    (net (code "147") (name "Net-(X25C-1)") (class "Default")
      (node (ref "U$8") (pin "1A") (pinfunction "1A_1A") (pintype "output"))
      (node (ref "X25") (pin "P$3") (pinfunction "1_P$3") (pintype "passive"))
    )
    (net (code "148") (name "Net-(X25D-1)") (class "Default")
      (node (ref "U$8") (pin "1B") (pinfunction "1B_1B") (pintype "output"))
      (node (ref "X25") (pin "P$4") (pinfunction "1_P$4") (pintype "passive"))
    )
    (net (code "149") (name "Net-(X33A-1)") (class "Default")
      (node (ref "U$9") (pin "2B") (pinfunction "2B_2B") (pintype "output"))
      (node (ref "X33") (pin "P$1") (pinfunction "1_P$1") (pintype "passive"))
    )
    (net (code "150") (name "Net-(X33B-1)") (class "Default")
      (node (ref "U$9") (pin "2A") (pinfunction "2A_2A") (pintype "output"))
      (node (ref "X33") (pin "P$2") (pinfunction "1_P$2") (pintype "passive"))
    )
    (net (code "151") (name "Net-(X33C-1)") (class "Default")
      (node (ref "U$9") (pin "1A") (pinfunction "1A_1A") (pintype "output"))
      (node (ref "X33") (pin "P$3") (pinfunction "1_P$3") (pintype "passive"))
    )
    (net (code "152") (name "Net-(X33D-1)") (class "Default")
      (node (ref "U$9") (pin "1B") (pinfunction "1B_1B") (pintype "output"))
      (node (ref "X33") (pin "P$4") (pinfunction "1_P$4") (pintype "passive"))
    )
    (net (code "153") (name "OUTPUT_LED_BOT_UP") (class "Default")
      (node (ref "R42") (pin "2") (pinfunction "2_2") (pintype "passive"))
      (node (ref "U1") (pin "61") (pinfunction "PD14_61") (pintype "bidirectional"))
    )
    (net (code "154") (name "OUTPUT_LED_TOP_DN") (class "Default")
      (node (ref "R43") (pin "2") (pinfunction "2_2") (pintype "passive"))
      (node (ref "U1") (pin "60") (pinfunction "PD13_60") (pintype "bidirectional"))
    )
    (net (code "155") (name "OUTPUT_LED_TRAY_1") (class "Default")
      (node (ref "R44") (pin "2") (pinfunction "2_2") (pintype "passive"))
      (node (ref "U1") (pin "59") (pinfunction "PD12_59") (pintype "bidirectional"))
    )
    (net (code "156") (name "OUTPUT_LED_TRAY_2") (class "Default")
      (node (ref "R45") (pin "2") (pinfunction "2_2") (pintype "passive"))
      (node (ref "U1") (pin "58") (pinfunction "PD11_58") (pintype "bidirectional"))
    )
    (net (code "157") (name "OUTPUT_PUMP") (class "Default")
      (node (ref "R40") (pin "2") (pinfunction "2_2") (pintype "passive"))
      (node (ref "U1") (pin "63") (pinfunction "PC6_63") (pintype "bidirectional"))
    )
    (net (code "158") (name "OUTPUT_VALVE") (class "Default")
      (node (ref "R41") (pin "2") (pinfunction "2_2") (pintype "passive"))
      (node (ref "U1") (pin "62") (pinfunction "PD15_62") (pintype "bidirectional"))
    )
    (net (code "159") (name "PA0{slash}ADC0") (class "Default")
      (node (ref "U1") (pin "23") (pinfunction "PA0_23") (pintype "bidirectional"))
      (node (ref "X27") (pin "P$1") (pinfunction "1_P$1") (pintype "passive"))
    )
    (net (code "160") (name "PA1{slash}ADC1") (class "Default")
      (node (ref "U1") (pin "24") (pinfunction "PA1_24") (pintype "bidirectional"))
      (node (ref "X27") (pin "P$2") (pinfunction "1_P$2") (pintype "passive"))
    )
    (net (code "161") (name "PA2{slash}ADC2") (class "Default")
      (node (ref "U1") (pin "25") (pinfunction "PA2_25") (pintype "bidirectional"))
      (node (ref "X27") (pin "P$3") (pinfunction "1_P$3") (pintype "passive"))
    )
    (net (code "162") (name "PA3{slash}ADC3") (class "Default")
      (node (ref "U1") (pin "26") (pinfunction "PA3_26") (pintype "bidirectional"))
      (node (ref "X27") (pin "P$4") (pinfunction "1_P$4") (pintype "passive"))
    )
    (net (code "163") (name "PA4") (class "Default")
      (node (ref "U1") (pin "29") (pinfunction "PA4_29") (pintype "bidirectional"))
      (node (ref "X28") (pin "P$1") (pinfunction "1_P$1") (pintype "passive"))
    )
    (net (code "164") (name "PA5{slash}SPI1_SCK") (class "Default")
      (node (ref "U1") (pin "30") (pinfunction "PA5_30") (pintype "bidirectional"))
      (node (ref "X26") (pin "P$2") (pinfunction "1_P$2") (pintype "passive"))
    )
    (net (code "165") (name "PA6{slash}SPI1_MISO") (class "Default")
      (node (ref "U1") (pin "31") (pinfunction "PA6_31") (pintype "bidirectional"))
      (node (ref "X26") (pin "P$3") (pinfunction "1_P$3") (pintype "passive"))
    )
    (net (code "166") (name "PA7{slash}SPI1_MOSI") (class "Default")
      (node (ref "U1") (pin "32") (pinfunction "PA7_32") (pintype "bidirectional"))
      (node (ref "X26") (pin "P$4") (pinfunction "1_P$4") (pintype "passive"))
    )
    (net (code "167") (name "PB0") (class "Default")
      (node (ref "U1") (pin "35") (pinfunction "PB0_35") (pintype "bidirectional"))
      (node (ref "X28") (pin "P$4") (pinfunction "1_P$4") (pintype "passive"))
    )
    (net (code "168") (name "PB6{slash}I2C1_SCL") (class "Default")
      (node (ref "R16") (pin "2") (pinfunction "2_2") (pintype "passive"))
      (node (ref "U1") (pin "92") (pinfunction "PB6_92") (pintype "bidirectional"))
      (node (ref "X19") (pin "P$1") (pinfunction "1_P$1") (pintype "passive"))
      (node (ref "X20") (pin "P$1") (pinfunction "1_P$1") (pintype "passive"))
    )
    (net (code "169") (name "PB7{slash}I2C1_SDA") (class "Default")
      (node (ref "R31") (pin "2") (pinfunction "2_2") (pintype "passive"))
      (node (ref "U1") (pin "93") (pinfunction "PB7_93") (pintype "bidirectional"))
      (node (ref "X19") (pin "P$2") (pinfunction "1_P$2") (pintype "passive"))
      (node (ref "X20") (pin "P$2") (pinfunction "1_P$2") (pintype "passive"))
    )
    (net (code "170") (name "PB12{slash}BUSY") (class "Default")
      (node (ref "R32") (pin "2") (pinfunction "2_2") (pintype "passive"))
      (node (ref "U1") (pin "51") (pinfunction "PB12_51") (pintype "bidirectional"))
      (node (ref "X19") (pin "P$3") (pinfunction "1_P$3") (pintype "passive"))
      (node (ref "X20") (pin "P$3") (pinfunction "1_P$3") (pintype "passive"))
    )
    (net (code "171") (name "PC4") (class "Default")
      (node (ref "U1") (pin "33") (pinfunction "PC4_33") (pintype "bidirectional"))
      (node (ref "X28") (pin "P$2") (pinfunction "1_P$2") (pintype "passive"))
    )
    (net (code "172") (name "PC5") (class "Default")
      (node (ref "U1") (pin "34") (pinfunction "PC5_34") (pintype "bidirectional"))
      (node (ref "X28") (pin "P$3") (pinfunction "1_P$3") (pintype "passive"))
    )
    (net (code "173") (name "RX") (class "Default")
      (node (ref "R1") (pin "2") (pinfunction "2_2") (pintype "passive"))
      (node (ref "R50") (pin "1") (pinfunction "1_1") (pintype "passive"))
      (node (ref "U1") (pin "69") (pinfunction "PA10_69") (pintype "bidirectional"))
    )
    (net (code "174") (name "SYS_JTC") (class "Default")
      (node (ref "U1") (pin "76") (pinfunction "PA14_76") (pintype "bidirectional"))
      (node (ref "X21") (pin "P$2") (pinfunction "1_P$2") (pintype "passive"))
    )
    (net (code "175") (name "SYS_JTMS-SWDIO") (class "Default")
      (node (ref "U1") (pin "72") (pinfunction "PA13_72") (pintype "bidirectional"))
      (node (ref "X21") (pin "P$1") (pinfunction "1_P$1") (pintype "passive"))
    )
    (net (code "176") (name "TX") (class "Default")
      (node (ref "R2") (pin "2") (pinfunction "2_2") (pintype "passive"))
      (node (ref "R51") (pin "1") (pinfunction "1_1") (pintype "passive"))
      (node (ref "U1") (pin "68") (pinfunction "PA9_68") (pintype "bidirectional"))
    )
    (net (code "178") (name "unconnected-(J1-ID-Pad4)") (class "Default")
      (node (ref "J1") (pin "4") (pinfunction "ID_4") (pintype "bidirectional"))
    )
    (net (code "179") (name "unconnected-(U1A-PA8-Pad67)") (class "Default")
      (node (ref "U1") (pin "67") (pinfunction "PA8_67") (pintype "bidirectional"))
    )
    (net (code "180") (name "unconnected-(U1A-PA12-Pad71)") (class "Default")
      (node (ref "U1") (pin "71") (pinfunction "PA12_71") (pintype "bidirectional"))
    )
    (net (code "181") (name "unconnected-(U1A-PA15-Pad77)") (class "Default")
      (node (ref "U1") (pin "77") (pinfunction "PA15_77") (pintype "bidirectional"))
    )
    (net (code "182") (name "unconnected-(U1A-PB3-Pad89)") (class "Default")
      (node (ref "U1") (pin "89") (pinfunction "PB3_89") (pintype "bidirectional"))
    )
    (net (code "183") (name "unconnected-(U1A-PB10-Pad47)") (class "Default")
      (node (ref "U1") (pin "47") (pinfunction "PB10_47") (pintype "bidirectional"))
    )
    (net (code "184") (name "unconnected-(U1A-PB15-Pad54)") (class "Default")
      (node (ref "U1") (pin "54") (pinfunction "PB15_54") (pintype "bidirectional"))
    )
    (net (code "185") (name "unconnected-(U1A-PC0-Pad15)") (class "Default")
      (node (ref "U1") (pin "15") (pinfunction "PC0_15") (pintype "bidirectional"))
    )
    (net (code "186") (name "unconnected-(U1A-PC1-Pad16)") (class "Default")
      (node (ref "U1") (pin "16") (pinfunction "PC1_16") (pintype "bidirectional"))
    )
    (net (code "187") (name "unconnected-(U1A-PC2-Pad17)") (class "Default")
      (node (ref "U1") (pin "17") (pinfunction "PC2_17") (pintype "bidirectional"))
    )
    (net (code "188") (name "unconnected-(U1A-PC3-Pad18)") (class "Default")
      (node (ref "U1") (pin "18") (pinfunction "PC3_18") (pintype "bidirectional"))
    )
    (net (code "189") (name "unconnected-(U1A-PC10-Pad78)") (class "Default")
      (node (ref "U1") (pin "78") (pinfunction "PC10_78") (pintype "bidirectional"))
    )
    (net (code "190") (name "unconnected-(U1A-PC13-Pad7)") (class "Default")
      (node (ref "U1") (pin "7") (pinfunction "PC13_7") (pintype "bidirectional"))
    )
    (net (code "191") (name "unconnected-(U1A-PC14-OSC32_IN-Pad8)") (class "Default")
      (node (ref "U1") (pin "8") (pinfunction "PC14-OSC32_IN_8") (pintype "bidirectional"))
    )
    (net (code "192") (name "unconnected-(U1A-PC15-OSC32_OUT-Pad9)") (class "Default")
      (node (ref "U1") (pin "9") (pinfunction "PC15-OSC32_OUT_9") (pintype "bidirectional"))
    )
    (net (code "193") (name "unconnected-(U1B-PE7-Pad38)") (class "Default")
      (node (ref "U1") (pin "38") (pinfunction "PE7_38") (pintype "bidirectional"))
    )
    (net (code "194") (name "unconnected-(U1B-PE8-Pad39)") (class "Default")
      (node (ref "U1") (pin "39") (pinfunction "PE8_39") (pintype "bidirectional"))
    )
    (net (code "195") (name "unconnected-(U1B-PE9-Pad40)") (class "Default")
      (node (ref "U1") (pin "40") (pinfunction "PE9_40") (pintype "bidirectional"))
    )
    (net (code "196") (name "unconnected-(U2-CTS#-Pad9)") (class "Default")
      (node (ref "U2") (pin "9") (pinfunction "CTS#_9") (pintype "bidirectional"))
    )
    (net (code "197") (name "unconnected-(U2-DCD#-Pad12)") (class "Default")
      (node (ref "U2") (pin "12") (pinfunction "DCD#_12") (pintype "bidirectional"))
    )
    (net (code "198") (name "unconnected-(U2-DSR#-Pad10)") (class "Default")
      (node (ref "U2") (pin "10") (pinfunction "DSR#_10") (pintype "bidirectional"))
    )
    (net (code "199") (name "unconnected-(U2-R232-Pad15)") (class "Default")
      (node (ref "U2") (pin "15") (pinfunction "R232_15") (pintype "bidirectional"))
    )
    (net (code "200") (name "unconnected-(U2-RI#-Pad11)") (class "Default")
      (node (ref "U2") (pin "11") (pinfunction "RI#_11") (pintype "bidirectional"))
    )
    (net (code "201") (name "unconnected-(U2-RTS#-Pad14)") (class "Default")
      (node (ref "U2") (pin "14") (pinfunction "RTS#_14") (pintype "bidirectional"))
    )
  )
)
